# TC264MCUV02.net
KiCad netlist of a schematic drawn in Altium Designer
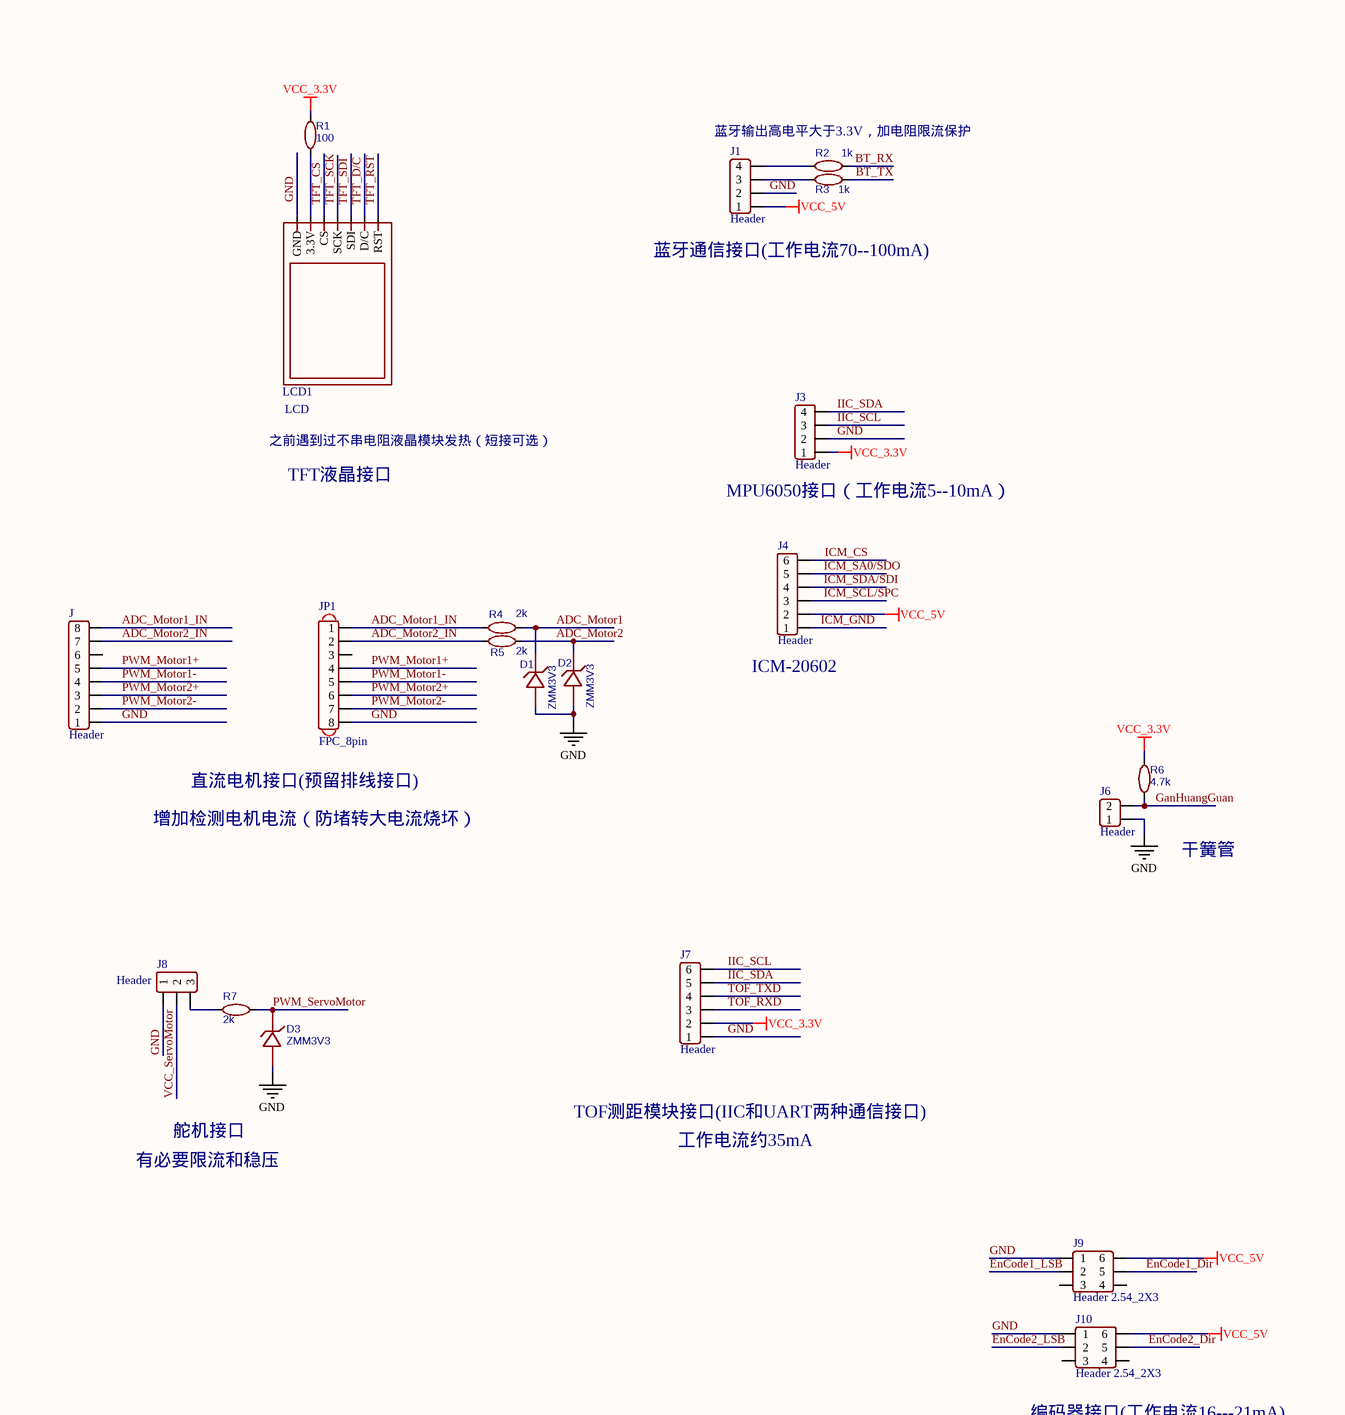
[diagram p0: TC264MCUV02.SchDoc, top left]
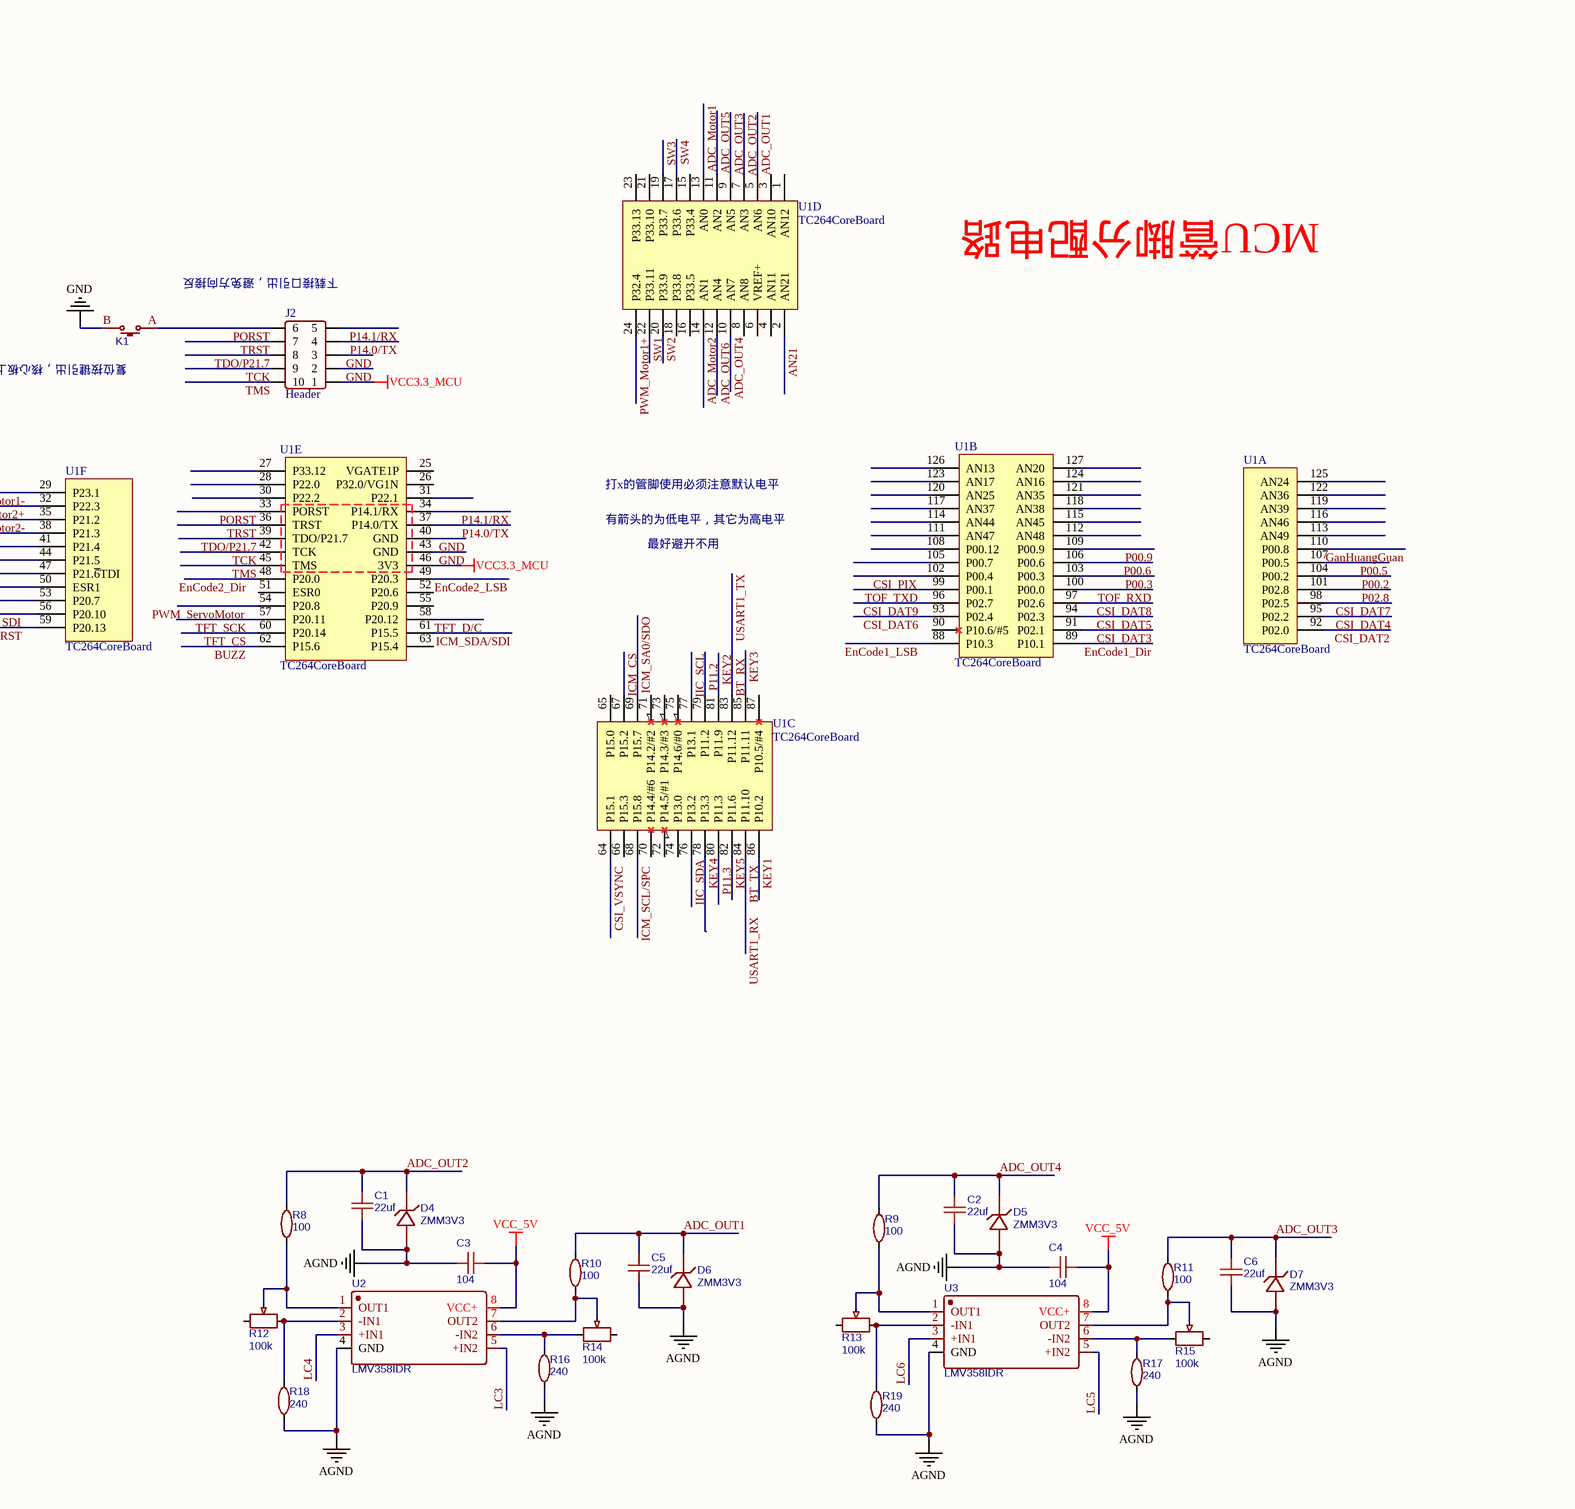
[diagram p1: TC264MCUV02.SchDoc, top right]
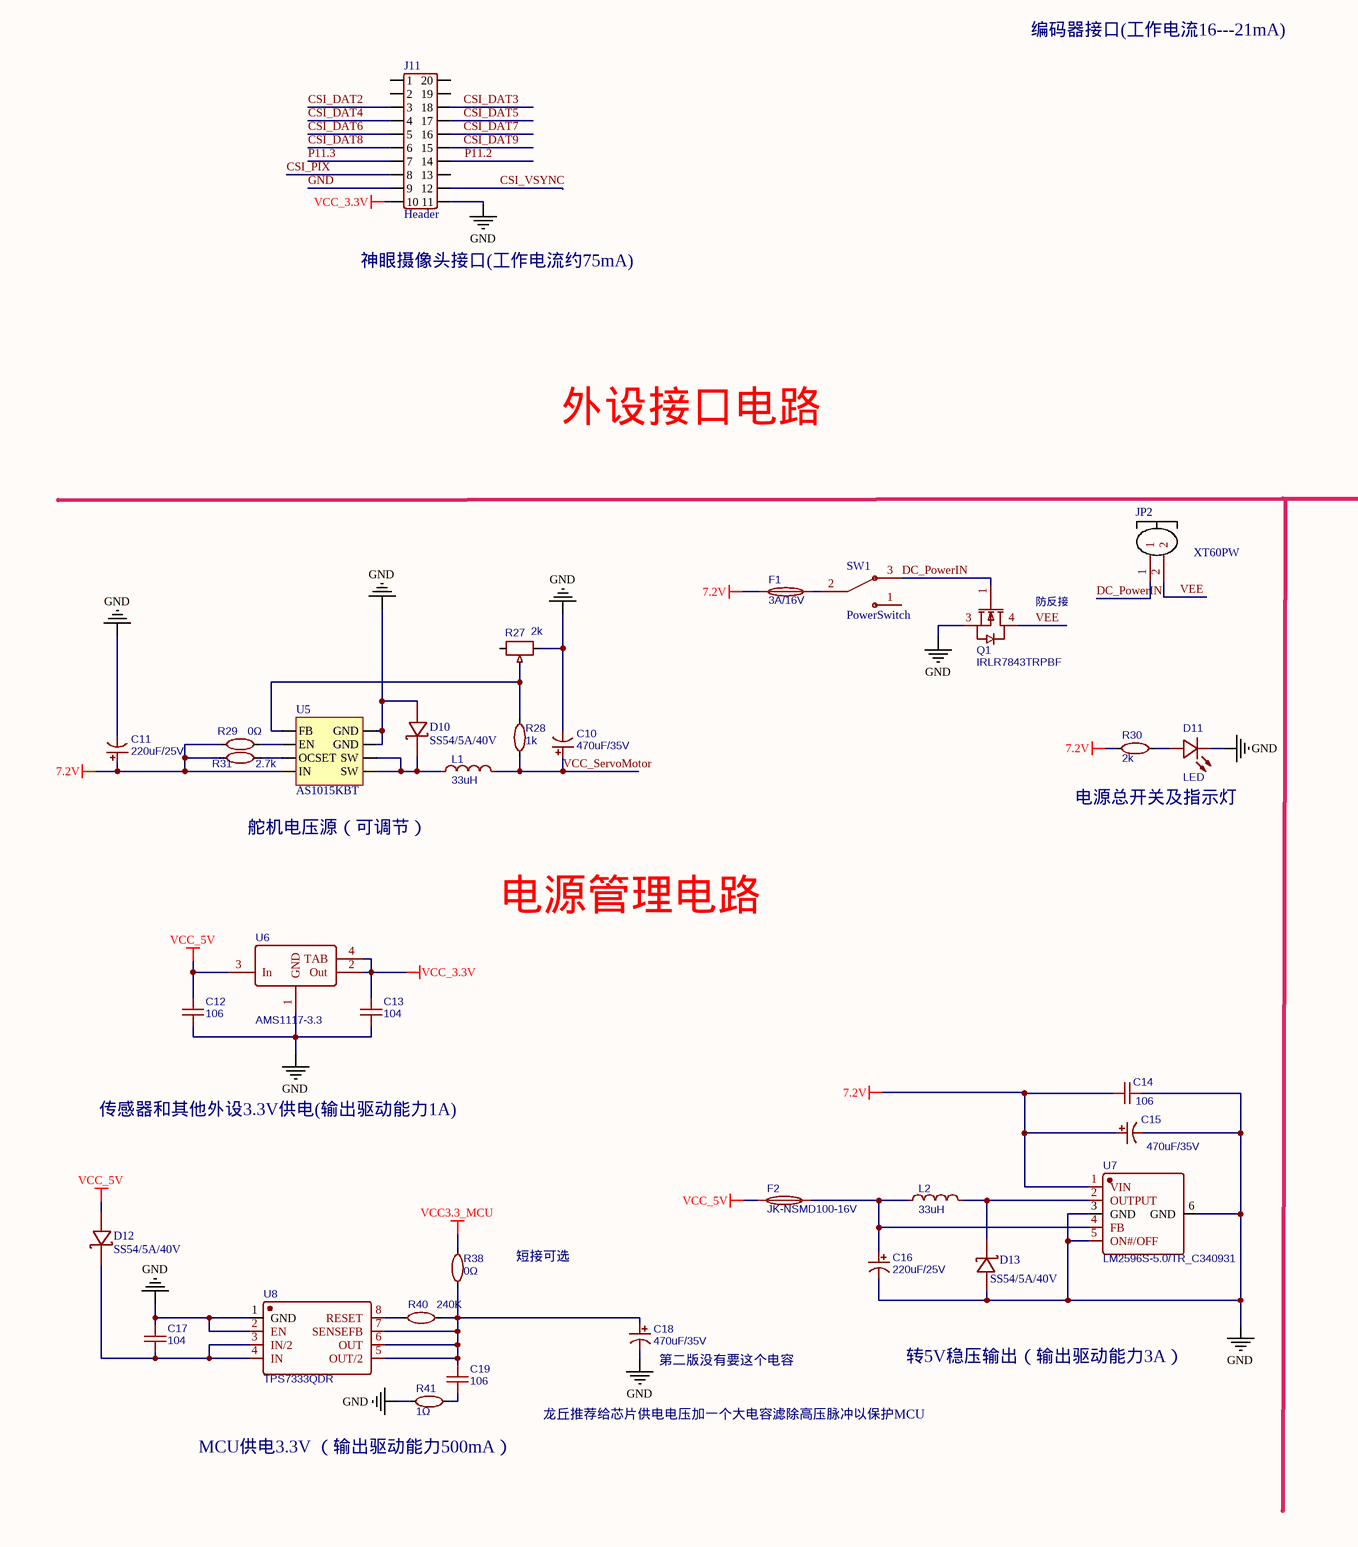
[diagram p2: TC264MCUV02.SchDoc, bottom left]
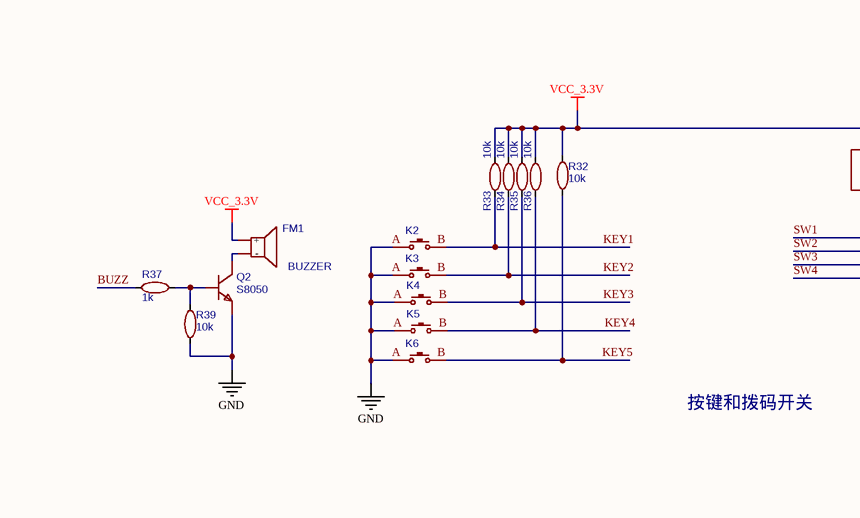
[diagram p3: TC264MCUV02.SchDoc, bottom middle]
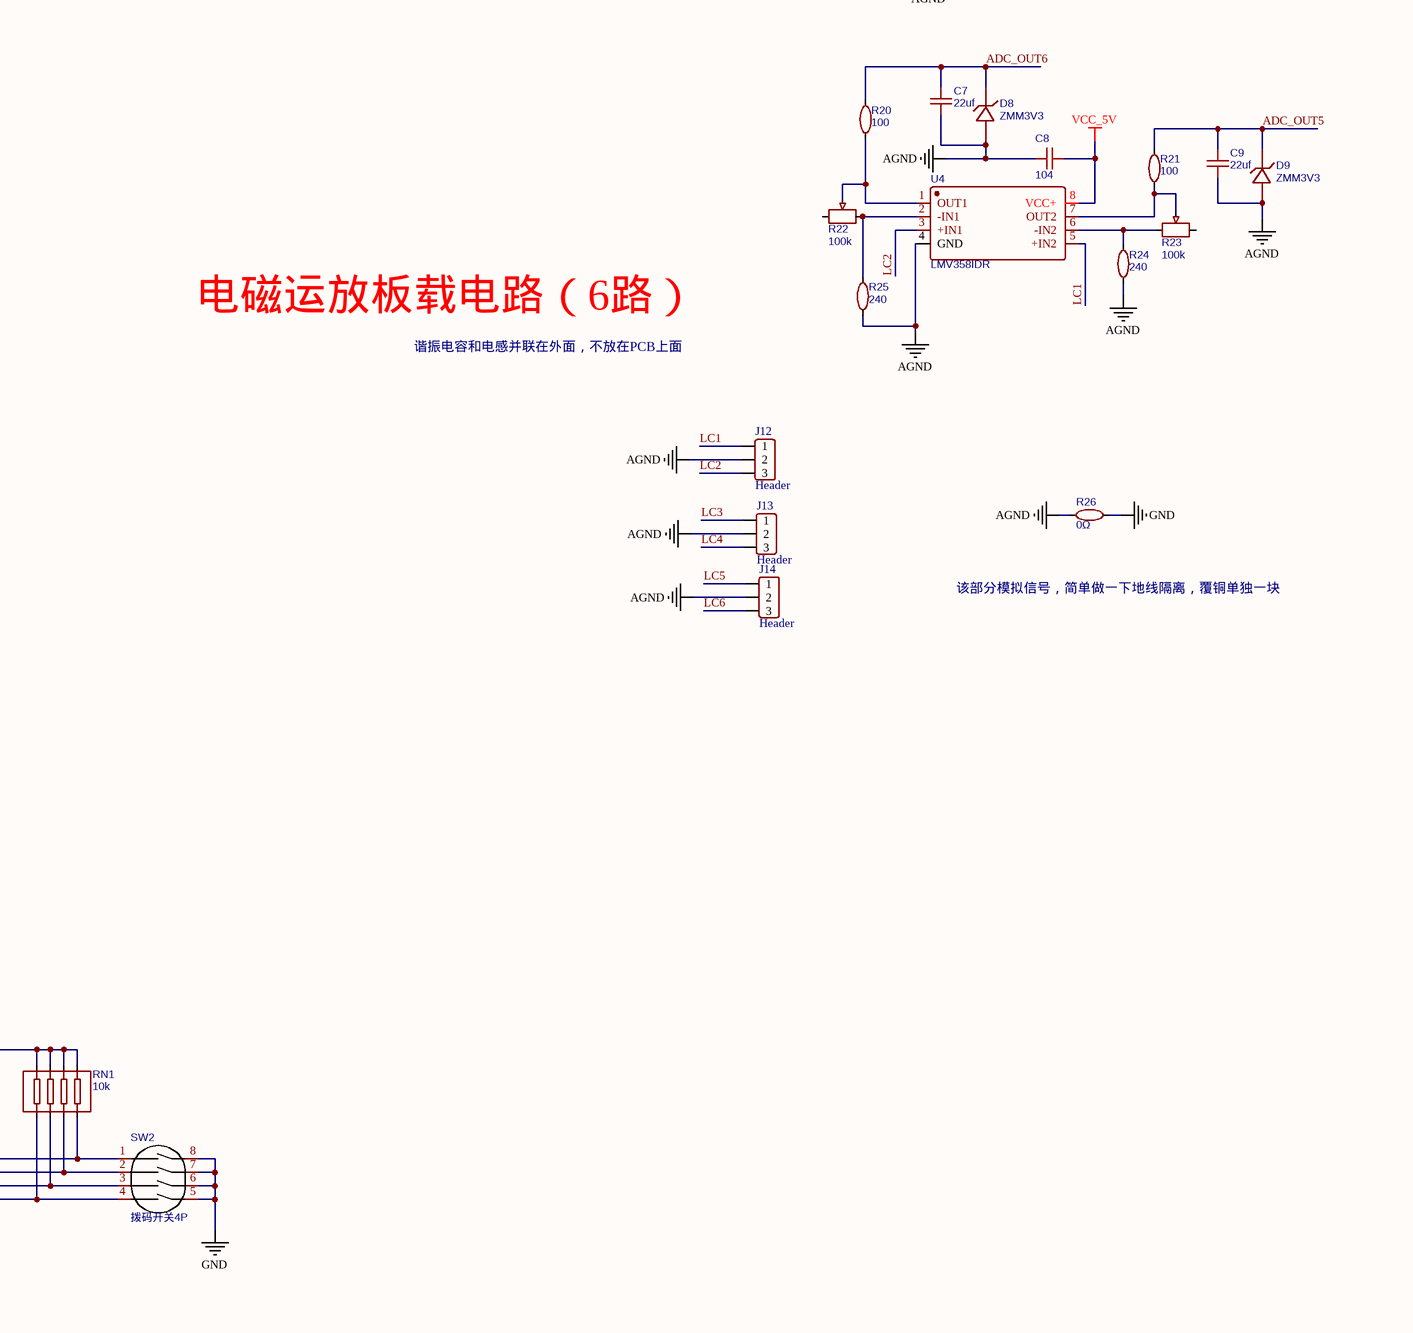
[diagram p4: TC264MCUV02.SchDoc, bottom right]

(export (version "E")
  (design (tool "Eeschema 10.0.6"))
  (components
    (comp (ref "C1")
      (value "22uf")
      (footprint "CAP_0603")
      (fields
        (field (name "BOM_SUPPLIER PART") "C307348")
        (field (name "BOM_MANUFACTURER PART") "CL10B104KB8WPNC")
        (field (name "CONTRIBUTOR") "LCSC")
      )
      (libsource (lib "LTC_Library1") (part "CAP_0603"))
    )
    (comp (ref "C2")
      (value "22uf")
      (footprint "CAP_0603")
      (fields
        (field (name "BOM_SUPPLIER PART") "C307348")
        (field (name "BOM_MANUFACTURER PART") "CL10B104KB8WPNC")
        (field (name "CONTRIBUTOR") "LCSC")
      )
      (libsource (lib "LTC_Library1") (part "CAP_0603"))
    )
    (comp (ref "C3")
      (value "104")
      (footprint "CAP_0603")
      (fields
        (field (name "BOM_SUPPLIER PART") "C307348")
        (field (name "BOM_MANUFACTURER PART") "CL10B104KB8WPNC")
        (field (name "CONTRIBUTOR") "LCSC")
      )
      (libsource (lib "LTC_Library1") (part "CAP_0603"))
    )
    (comp (ref "C4")
      (value "104")
      (footprint "CAP_0603")
      (fields
        (field (name "BOM_SUPPLIER PART") "C307348")
        (field (name "BOM_MANUFACTURER PART") "CL10B104KB8WPNC")
        (field (name "CONTRIBUTOR") "LCSC")
      )
      (libsource (lib "LTC_Library1") (part "CAP_0603"))
    )
    (comp (ref "C5")
      (value "22uf")
      (footprint "CAP_0603")
      (fields
        (field (name "BOM_SUPPLIER PART") "C307348")
        (field (name "BOM_MANUFACTURER PART") "CL10B104KB8WPNC")
        (field (name "CONTRIBUTOR") "LCSC")
      )
      (libsource (lib "LTC_Library1") (part "CAP_0603"))
    )
    (comp (ref "C6")
      (value "22uf")
      (footprint "CAP_0603")
      (fields
        (field (name "BOM_SUPPLIER PART") "C307348")
        (field (name "BOM_MANUFACTURER PART") "CL10B104KB8WPNC")
        (field (name "CONTRIBUTOR") "LCSC")
      )
      (libsource (lib "LTC_Library1") (part "CAP_0603"))
    )
    (comp (ref "C7")
      (value "22uf")
      (footprint "CAP_0603")
      (fields
        (field (name "BOM_SUPPLIER PART") "C307348")
        (field (name "BOM_MANUFACTURER PART") "CL10B104KB8WPNC")
        (field (name "CONTRIBUTOR") "LCSC")
      )
      (libsource (lib "LTC_Library1") (part "CAP_0603"))
    )
    (comp (ref "C8")
      (value "104")
      (footprint "CAP_0603")
      (fields
        (field (name "BOM_SUPPLIER PART") "C307348")
        (field (name "BOM_MANUFACTURER PART") "CL10B104KB8WPNC")
        (field (name "CONTRIBUTOR") "LCSC")
      )
      (libsource (lib "LTC_Library1") (part "CAP_0603"))
    )
    (comp (ref "C9")
      (value "22uf")
      (footprint "CAP_0603")
      (fields
        (field (name "BOM_SUPPLIER PART") "C307348")
        (field (name "BOM_MANUFACTURER PART") "CL10B104KB8WPNC")
        (field (name "CONTRIBUTOR") "LCSC")
      )
      (libsource (lib "LTC_Library1") (part "CAP_0603"))
    )
    (comp (ref "C10")
      (value "470uF/35V")
      (footprint "CAPE_SMD_F_8.4")
      (description "贴片电解电容")
      (fields
        (field (name "BOM_MANUFACTURER PART") "RVT1C221M0607")
        (field (name "BOM_SUPPLIER PART") "C72496")
      )
      (libsource (lib "") (part "CAP_E_SMD_1"))
    )
    (comp (ref "C11")
      (value "220uF/25V")
      (footprint "CAPE_SMD_F_8.4")
      (description "贴片电解电容")
      (fields
        (field (name "BOM_MANUFACTURER PART") "RVT1C221M0607")
        (field (name "BOM_SUPPLIER PART") "C72496")
      )
      (libsource (lib "") (part "CAP_E_SMD_1"))
    )
    (comp (ref "C12")
      (value "106")
      (footprint "CAP_0603")
      (fields
        (field (name "BOM_SUPPLIER PART") "C307348")
        (field (name "BOM_MANUFACTURER PART") "CL10B104KB8WPNC")
        (field (name "CONTRIBUTOR") "LCSC")
      )
      (libsource (lib "LTC_Library1") (part "CAP_0603"))
    )
    (comp (ref "C13")
      (value "104")
      (footprint "CAP_0603")
      (fields
        (field (name "BOM_SUPPLIER PART") "C307348")
        (field (name "BOM_MANUFACTURER PART") "CL10B104KB8WPNC")
        (field (name "CONTRIBUTOR") "LCSC")
      )
      (libsource (lib "LTC_Library1") (part "CAP_0603"))
    )
    (comp (ref "C14")
      (value "106")
      (footprint "CAP_0603")
      (fields
        (field (name "BOM_SUPPLIER PART") "C307348")
        (field (name "BOM_MANUFACTURER PART") "CL10B104KB8WPNC")
        (field (name "CONTRIBUTOR") "LCSC")
      )
      (libsource (lib "LTC_Library1") (part "CAP_0603"))
    )
    (comp (ref "C15")
      (value "470uF/35V")
      (footprint "CAPE_SMD_G_10.6")
      (description "贴片电解电容")
      (fields
        (field (name "BOM_MANUFACTURER PART") "RVT1C221M0607")
        (field (name "BOM_SUPPLIER PART") "C72496")
      )
      (libsource (lib "LTC_Library1") (part "CAP_E_SMD"))
    )
    (comp (ref "C16")
      (value "220uF/25V")
      (footprint "CAPE_SMD_F_8.4")
      (description "贴片电解电容")
      (fields
        (field (name "BOM_MANUFACTURER PART") "RVT1C221M0607")
        (field (name "BOM_SUPPLIER PART") "C72496")
      )
      (libsource (lib "") (part "CAP_E_SMD_1"))
    )
    (comp (ref "C17")
      (value "104")
      (footprint "CAP_0603")
      (fields
        (field (name "BOM_SUPPLIER PART") "C307348")
        (field (name "BOM_MANUFACTURER PART") "CL10B104KB8WPNC")
        (field (name "CONTRIBUTOR") "LCSC")
      )
      (libsource (lib "LTC_Library1") (part "CAP_0603"))
    )
    (comp (ref "C18")
      (value "470uF/35V")
      (footprint "CAPE_SMD_G_10.6")
      (description "贴片电解电容")
      (fields
        (field (name "BOM_MANUFACTURER PART") "RVT1C221M0607")
        (field (name "BOM_SUPPLIER PART") "C72496")
      )
      (libsource (lib "") (part "CAP_E_SMD_1"))
    )
    (comp (ref "C19")
      (value "106")
      (footprint "CAP_0603")
      (fields
        (field (name "BOM_SUPPLIER PART") "C307348")
        (field (name "BOM_MANUFACTURER PART") "CL10B104KB8WPNC")
        (field (name "CONTRIBUTOR") "LCSC")
      )
      (libsource (lib "LTC_Library1") (part "CAP_0603"))
    )
    (comp (ref "D1")
      (value "ZMM3V3")
      (footprint "LL-34_L3.5-W1.5-RD")
      (fields (field (name "BOM_SUPPLIER PART") "C8056"))
      (libsource (lib "SmartCar_Library") (part "ZMM3V3"))
    )
    (comp (ref "D2")
      (value "ZMM3V3")
      (footprint "LL-34_L3.5-W1.5-RD")
      (fields (field (name "BOM_SUPPLIER PART") "C8056"))
      (libsource (lib "SmartCar_Library") (part "ZMM3V3"))
    )
    (comp (ref "D3")
      (value "ZMM3V3")
      (footprint "LL-34_L3.5-W1.5-RD")
      (fields (field (name "BOM_SUPPLIER PART") "C8056"))
      (libsource (lib "SmartCar_Library") (part "ZMM3V3"))
    )
    (comp (ref "D4")
      (value "ZMM3V3")
      (footprint "LL-34_L3.5-W1.5-RD")
      (fields (field (name "BOM_SUPPLIER PART") "C8056"))
      (libsource (lib "SmartCar_Library") (part "ZMM3V3"))
    )
    (comp (ref "D5")
      (value "ZMM3V3")
      (footprint "LL-34_L3.5-W1.5-RD")
      (fields (field (name "BOM_SUPPLIER PART") "C8056"))
      (libsource (lib "SmartCar_Library") (part "ZMM3V3"))
    )
    (comp (ref "D6")
      (value "ZMM3V3")
      (footprint "LL-34_L3.5-W1.5-RD")
      (fields (field (name "BOM_SUPPLIER PART") "C8056"))
      (libsource (lib "SmartCar_Library") (part "ZMM3V3"))
    )
    (comp (ref "D7")
      (value "ZMM3V3")
      (footprint "LL-34_L3.5-W1.5-RD")
      (fields (field (name "BOM_SUPPLIER PART") "C8056"))
      (libsource (lib "SmartCar_Library") (part "ZMM3V3"))
    )
    (comp (ref "D8")
      (value "ZMM3V3")
      (footprint "LL-34_L3.5-W1.5-RD")
      (fields (field (name "BOM_SUPPLIER PART") "C8056"))
      (libsource (lib "SmartCar_Library") (part "ZMM3V3"))
    )
    (comp (ref "D9")
      (value "ZMM3V3")
      (footprint "LL-34_L3.5-W1.5-RD")
      (fields (field (name "BOM_SUPPLIER PART") "C8056"))
      (libsource (lib "SmartCar_Library") (part "ZMM3V3"))
    )
    (comp (ref "D10")
      (value "SS54/5A/40V")
      (footprint "DO214_SMA")
      (libsource (lib "LTC_Library1") (part "SS54"))
    )
    (comp (ref "D11")
      (value "LED")
      (footprint "LED_0603_B")
      (description "发光LED")
      (fields
        (field (name "BOM_MANUFACTURER PART") "D-G080508G1")
        (field (name "BOM_SUPPLIER PART") "C107402")
        (field (name "CONTRIBUTOR") "LCSC")
      )
      (libsource (lib "LTC_Library1") (part "LED_0603"))
    )
    (comp (ref "D12")
      (value "SS54/5A/40V")
      (footprint "DO214_SMA")
      (libsource (lib "LTC_Library1") (part "SS54"))
    )
    (comp (ref "D13")
      (value "SS54/5A/40V")
      (footprint "DO214_SMA")
      (libsource (lib "LTC_Library1") (part "SS54"))
    )
    (comp (ref "F1")
      (value "3A/16V")
      (footprint "FUSE_1210")
      (fields
        (field (name "BOM_SUPPLIER PART") "C369161")
        (field (name "BOM_MANUFACTURER PART") "JK-NSMD100-16V")
        (field (name "CONTRIBUTOR") "LCSC")
      )
      (libsource (lib "SmartCar_Library") (part "JK-NSMD100-16V"))
    )
    (comp (ref "F2")
      (value "JK-NSMD100-16V")
      (footprint "F1206")
      (fields (field (name "BOM_SUPPLIER PART") "C369161") (field (name "CONTRIBUTOR") "LCSC"))
      (libsource (lib "SmartCar_Library") (part "JK-NSMD100-16V"))
    )
    (comp (ref "FM1")
      (value "BUZZER")
      (footprint "BUZZ-12*7.5")
      (description "蜂鸣器")
      (fields (field (name "BOM_MANUFACTURER PART") "TMB12A12") (field (name "BOM_SUPPLIER PART") "C96079"))
      (libsource (lib "LTC_Library1") (part "BUZZER"))
    )
    (comp (ref "J")
      (value "Header")
      (footprint "Header 2.54X8")
      (libsource (lib "LTC_Library1") (part "Header 2.54_8"))
    )
    (comp (ref "J1")
      (value "Header")
      (footprint "Header F 2.54X4")
      (libsource (lib "LTC_Library1") (part "Header 2.54_4"))
    )
    (comp (ref "J2")
      (value "Header")
      (footprint "IDC_10P")
      (libsource (lib "Headers") (part "Header 2.54_2X5"))
    )
    (comp (ref "J3")
      (value "Header")
      (footprint "Header 2.54X4")
      (libsource (lib "LTC_Library1") (part "Header 2.54_4"))
    )
    (comp (ref "J4")
      (value "Header")
      (footprint "Header 2.54X6")
      (libsource (lib "LTC_Library1") (part "Header 2.54_6"))
    )
    (comp (ref "J6")
      (value "Header")
      (footprint "HX2.54-2")
      (libsource (lib "LTC_Library1") (part "Header 2.54_2"))
    )
    (comp (ref "J7")
      (value "Header")
      (footprint "Header 2.54X6")
      (libsource (lib "LTC_Library1") (part "Header 2.54_6"))
    )
    (comp (ref "J8")
      (value "Header")
      (footprint "Header 2.54X3")
      (libsource (lib "LTC_Library1") (part "Header 2.54_3"))
    )
    (comp (ref "J9")
      (value "Header 2.54_2X3")
      (footprint "IDC_6P")
      (libsource (lib "Headers") (part "Header 2.54_2X3"))
    )
    (comp (ref "J10")
      (value "Header 2.54_2X3")
      (footprint "IDC_6P")
      (libsource (lib "Headers") (part "Header 2.54_2X3"))
    )
    (comp (ref "J11")
      (value "Header")
      (footprint "Header F 2.54_2x10")
      (libsource (lib "LTC_Library1") (part "Header 2.54_2X10"))
    )
    (comp (ref "J12")
      (value "Header")
      (footprint "Header 2.54X3")
      (libsource (lib "LTC_Library1") (part "Header 2.54_3"))
    )
    (comp (ref "J13")
      (value "Header")
      (footprint "Header 2.54X3")
      (libsource (lib "LTC_Library1") (part "Header 2.54_3"))
    )
    (comp (ref "J14")
      (value "Header")
      (footprint "Header 2.54X3")
      (libsource (lib "LTC_Library1") (part "Header 2.54_3"))
    )
    (comp (ref "JP1")
      (value "FPC_8pin")
      (footprint "FPC_1.0_8P")
      (libsource (lib "LTC_Library1") (part "FPC_8pin"))
    )
    (comp (ref "JP2")
      (value "XT60PW")
      (footprint "XT60PW")
      (libsource (lib "SmartCar_Library") (part "XT60PW"))
    )
    (comp (ref "K1")
      (value "TS-Button_2P")
      (footprint "SW_SMD_6.1*3.7")
      (description "贴片按键 3*6*2.5")
      (fields
        (field (name "BOM_SUPPLIER PART") "C455236")
        (field (name "BOM_MANUFACTURER PART") "TS-1007S-26")
        (field (name "CONTRIBUTOR") "LCSC")
      )
      (libsource (lib "LTC_Library1") (part "TS-Button_2P"))
    )
    (comp (ref "K2")
      (value "TS-Button_2P")
      (footprint "SW_SMD_6.1*3.7")
      (description "贴片按键 3*6*2.5")
      (fields
        (field (name "BOM_SUPPLIER PART") "C455236")
        (field (name "BOM_MANUFACTURER PART") "TS-1007S-26")
        (field (name "CONTRIBUTOR") "LCSC")
      )
      (libsource (lib "LTC_Library1") (part "TS-Button_2P"))
    )
    (comp (ref "K3")
      (value "TS-Button_2P")
      (footprint "SW_SMD_6.1*3.7")
      (description "贴片按键 3*6*2.5")
      (fields
        (field (name "BOM_SUPPLIER PART") "C455236")
        (field (name "BOM_MANUFACTURER PART") "TS-1007S-26")
        (field (name "CONTRIBUTOR") "LCSC")
      )
      (libsource (lib "LTC_Library1") (part "TS-Button_2P"))
    )
    (comp (ref "K4")
      (value "TS-Button_2P")
      (footprint "SW_SMD_6.1*3.7")
      (description "贴片按键 3*6*2.5")
      (fields
        (field (name "BOM_SUPPLIER PART") "C455236")
        (field (name "BOM_MANUFACTURER PART") "TS-1007S-26")
        (field (name "CONTRIBUTOR") "LCSC")
      )
      (libsource (lib "LTC_Library1") (part "TS-Button_2P"))
    )
    (comp (ref "K5")
      (value "TS-Button_2P")
      (footprint "SW_SMD_6.1*3.7")
      (description "贴片按键 3*6*2.5")
      (fields
        (field (name "BOM_SUPPLIER PART") "C455236")
        (field (name "BOM_MANUFACTURER PART") "TS-1007S-26")
        (field (name "CONTRIBUTOR") "LCSC")
      )
      (libsource (lib "LTC_Library1") (part "TS-Button_2P"))
    )
    (comp (ref "K6")
      (value "TS-Button_2P")
      (footprint "SW_SMD_6.1*3.7")
      (description "贴片按键 3*6*2.5")
      (fields
        (field (name "BOM_SUPPLIER PART") "C455236")
        (field (name "BOM_MANUFACTURER PART") "TS-1007S-26")
        (field (name "CONTRIBUTOR") "LCSC")
      )
      (libsource (lib "LTC_Library1") (part "TS-Button_2P"))
    )
    (comp (ref "L1")
      (value "33uH")
      (footprint "IND-SMD_L8.0-W8.0")
      (fields
        (field (name "BOM_SUPPLIER PART") "C295130")
        (field (name "BOM_MANUFACTURER PART") "NLV25T-330J-EF")
        (field (name "CONTRIBUTOR") "LCSC")
      )
      (libsource (lib "SmartCar_Library") (part "Inductor"))
    )
    (comp (ref "L2")
      (value "33uH")
      (footprint "IND-SMD_L8.0-W8.0")
      (fields
        (field (name "BOM_SUPPLIER PART") "C295130")
        (field (name "BOM_MANUFACTURER PART") "NLV25T-330J-EF")
        (field (name "CONTRIBUTOR") "LCSC")
      )
      (libsource (lib "SmartCar_Library") (part "Inductor"))
    )
    (comp (ref "LCD1")
      (value "LCD")
      (footprint "TFT_LCD")
      (libsource (lib "SmartCar_Library") (part "TFT-LCD"))
    )
    (comp (ref "Q1")
      (value "IRLR7843TRPBF")
      (footprint "TO-252-2")
      (description "MOS管")
      (fields (field (name "BOM_SUPPLIER PART") "C21988"))
      (libsource (lib "LTC_Library1") (part "IRLR7843TRPBF"))
    )
    (comp (ref "Q2")
      (value "S8050")
      (footprint "SOT-23-3")
      (description "三极管NPN")
      (fields
        (field (name "BOM_MANUFACTURER PART") "FHT9014Y-ME")
        (field (name "BOM_SUPPLIER PART") "C88861")
      )
      (libsource (lib "LTC_Library1") (part "S8050"))
    )
    (comp (ref "R1")
      (value "100")
      (footprint "RES_0603")
      (fields
        (field (name "BOM_MANUFACTURER PART") "RC0402JR-07100KL")
        (field (name "BOM_SUPPLIER PART") "C106234")
      )
      (libsource (lib "LTC_Library1") (part "RES_0603"))
    )
    (comp (ref "R2")
      (value "1k")
      (footprint "RES_0603")
      (fields
        (field (name "BOM_MANUFACTURER PART") "RC0402JR-07100KL")
        (field (name "BOM_SUPPLIER PART") "C106234")
      )
      (libsource (lib "LTC_Library1") (part "RES_0603"))
    )
    (comp (ref "R3")
      (value "1k")
      (footprint "RES_0603")
      (fields
        (field (name "BOM_MANUFACTURER PART") "RC0402JR-07100KL")
        (field (name "BOM_SUPPLIER PART") "C106234")
      )
      (libsource (lib "LTC_Library1") (part "RES_0603"))
    )
    (comp (ref "R4")
      (value "2k")
      (footprint "RES_0603")
      (fields
        (field (name "BOM_MANUFACTURER PART") "RC0402JR-07100KL")
        (field (name "BOM_SUPPLIER PART") "C106234")
      )
      (libsource (lib "LTC_Library1") (part "RES_0603"))
    )
    (comp (ref "R5")
      (value "2k")
      (footprint "RES_0603")
      (fields
        (field (name "BOM_MANUFACTURER PART") "RC0402JR-07100KL")
        (field (name "BOM_SUPPLIER PART") "C106234")
      )
      (libsource (lib "LTC_Library1") (part "RES_0603"))
    )
    (comp (ref "R6")
      (value "4.7k")
      (footprint "RES_0603")
      (fields
        (field (name "BOM_MANUFACTURER PART") "RC0402JR-07100KL")
        (field (name "BOM_SUPPLIER PART") "C106234")
      )
      (libsource (lib "LTC_Library1") (part "RES_0603"))
    )
    (comp (ref "R7")
      (value "2k")
      (footprint "RES_0603")
      (fields
        (field (name "BOM_MANUFACTURER PART") "RC0402JR-07100KL")
        (field (name "BOM_SUPPLIER PART") "C106234")
      )
      (libsource (lib "LTC_Library1") (part "RES_0603"))
    )
    (comp (ref "R8")
      (value "100")
      (footprint "RES_0603")
      (fields
        (field (name "BOM_MANUFACTURER PART") "RC0402JR-07100KL")
        (field (name "BOM_SUPPLIER PART") "C106234")
      )
      (libsource (lib "LTC_Library1") (part "RES_0603"))
    )
    (comp (ref "R9")
      (value "100")
      (footprint "RES_0603")
      (fields
        (field (name "BOM_MANUFACTURER PART") "RC0402JR-07100KL")
        (field (name "BOM_SUPPLIER PART") "C106234")
      )
      (libsource (lib "LTC_Library1") (part "RES_0603"))
    )
    (comp (ref "R10")
      (value "100")
      (footprint "RES_0603")
      (fields
        (field (name "BOM_MANUFACTURER PART") "RC0402JR-07100KL")
        (field (name "BOM_SUPPLIER PART") "C106234")
      )
      (libsource (lib "LTC_Library1") (part "RES_0603"))
    )
    (comp (ref "R11")
      (value "100")
      (footprint "RES_0603")
      (fields
        (field (name "BOM_MANUFACTURER PART") "RC0402JR-07100KL")
        (field (name "BOM_SUPPLIER PART") "C106234")
      )
      (libsource (lib "LTC_Library1") (part "RES_0603"))
    )
    (comp (ref "R12")
      (value "100k")
      (footprint "RES_POT-3296W")
      (description "可调电阻3296W")
      (fields
        (field (name "BOM_SUPPLIER PART") "C118963")
        (field (name "BOM_MANUFACTURER PART") "3296W-1-104")
        (field (name "CONTRIBUTOR") "LCSC")
      )
      (libsource (lib "LTC_Library1") (part "RES_POT-3296W"))
    )
    (comp (ref "R13")
      (value "100k")
      (footprint "RES_POT-3296W")
      (description "可调电阻3296W")
      (fields
        (field (name "BOM_SUPPLIER PART") "C118963")
        (field (name "BOM_MANUFACTURER PART") "3296W-1-104")
        (field (name "CONTRIBUTOR") "LCSC")
      )
      (libsource (lib "LTC_Library1") (part "RES_POT-3296W"))
    )
    (comp (ref "R14")
      (value "100k")
      (footprint "RES_POT-3296W")
      (description "可调电阻3296W")
      (fields
        (field (name "BOM_SUPPLIER PART") "C118963")
        (field (name "BOM_MANUFACTURER PART") "3296W-1-104")
        (field (name "CONTRIBUTOR") "LCSC")
      )
      (libsource (lib "LTC_Library1") (part "RES_POT-3296W"))
    )
    (comp (ref "R15")
      (value "100k")
      (footprint "RES_POT-3296W")
      (description "可调电阻3296W")
      (fields
        (field (name "BOM_SUPPLIER PART") "C118963")
        (field (name "BOM_MANUFACTURER PART") "3296W-1-104")
        (field (name "CONTRIBUTOR") "LCSC")
      )
      (libsource (lib "LTC_Library1") (part "RES_POT-3296W"))
    )
    (comp (ref "R16")
      (value "240")
      (footprint "RES_0603")
      (fields
        (field (name "BOM_MANUFACTURER PART") "RC0402JR-07100KL")
        (field (name "BOM_SUPPLIER PART") "C106234")
      )
      (libsource (lib "LTC_Library1") (part "RES_0603"))
    )
    (comp (ref "R17")
      (value "240")
      (footprint "RES_0603")
      (fields
        (field (name "BOM_MANUFACTURER PART") "RC0402JR-07100KL")
        (field (name "BOM_SUPPLIER PART") "C106234")
      )
      (libsource (lib "LTC_Library1") (part "RES_0603"))
    )
    (comp (ref "R18")
      (value "240")
      (footprint "RES_0603")
      (fields
        (field (name "BOM_MANUFACTURER PART") "RC0402JR-07100KL")
        (field (name "BOM_SUPPLIER PART") "C106234")
      )
      (libsource (lib "LTC_Library1") (part "RES_0603"))
    )
    (comp (ref "R19")
      (value "240")
      (footprint "RES_0603")
      (fields
        (field (name "BOM_MANUFACTURER PART") "RC0402JR-07100KL")
        (field (name "BOM_SUPPLIER PART") "C106234")
      )
      (libsource (lib "LTC_Library1") (part "RES_0603"))
    )
    (comp (ref "R20")
      (value "100")
      (footprint "RES_0603")
      (fields
        (field (name "BOM_MANUFACTURER PART") "RC0402JR-07100KL")
        (field (name "BOM_SUPPLIER PART") "C106234")
      )
      (libsource (lib "LTC_Library1") (part "RES_0603"))
    )
    (comp (ref "R21")
      (value "100")
      (footprint "RES_0603")
      (fields
        (field (name "BOM_MANUFACTURER PART") "RC0402JR-07100KL")
        (field (name "BOM_SUPPLIER PART") "C106234")
      )
      (libsource (lib "LTC_Library1") (part "RES_0603"))
    )
    (comp (ref "R22")
      (value "100k")
      (footprint "RES_POT-3296W")
      (description "可调电阻3296W")
      (fields
        (field (name "BOM_SUPPLIER PART") "C118963")
        (field (name "BOM_MANUFACTURER PART") "3296W-1-104")
        (field (name "CONTRIBUTOR") "LCSC")
      )
      (libsource (lib "LTC_Library1") (part "RES_POT-3296W"))
    )
    (comp (ref "R23")
      (value "100k")
      (footprint "RES_POT-3296W")
      (description "可调电阻3296W")
      (fields
        (field (name "BOM_SUPPLIER PART") "C118963")
        (field (name "BOM_MANUFACTURER PART") "3296W-1-104")
        (field (name "CONTRIBUTOR") "LCSC")
      )
      (libsource (lib "LTC_Library1") (part "RES_POT-3296W"))
    )
    (comp (ref "R24")
      (value "240")
      (footprint "RES_0603")
      (fields
        (field (name "BOM_MANUFACTURER PART") "RC0402JR-07100KL")
        (field (name "BOM_SUPPLIER PART") "C106234")
      )
      (libsource (lib "LTC_Library1") (part "RES_0603"))
    )
    (comp (ref "R25")
      (value "240")
      (footprint "RES_0603")
      (fields
        (field (name "BOM_MANUFACTURER PART") "RC0402JR-07100KL")
        (field (name "BOM_SUPPLIER PART") "C106234")
      )
      (libsource (lib "LTC_Library1") (part "RES_0603"))
    )
    (comp (ref "R26")
      (value "0Ω")
      (footprint "RES_0603")
      (fields
        (field (name "BOM_MANUFACTURER PART") "RC0402JR-07100KL")
        (field (name "BOM_SUPPLIER PART") "C106234")
      )
      (libsource (lib "LTC_Library1") (part "RES_0603"))
    )
    (comp (ref "R27")
      (value "2k")
      (footprint "RES_POT-3296W")
      (description "可调电阻3296W")
      (fields
        (field (name "BOM_SUPPLIER PART") "C118963")
        (field (name "BOM_MANUFACTURER PART") "3296W-1-104")
        (field (name "CONTRIBUTOR") "LCSC")
      )
      (libsource (lib "LTC_Library1") (part "RES_POT-3296W"))
    )
    (comp (ref "R28")
      (value "1k")
      (footprint "RES_0603")
      (fields
        (field (name "BOM_MANUFACTURER PART") "RC0402JR-07100KL")
        (field (name "BOM_SUPPLIER PART") "C106234")
      )
      (libsource (lib "LTC_Library1") (part "RES_0603"))
    )
    (comp (ref "R29")
      (value "0Ω")
      (footprint "RES_0603")
      (fields
        (field (name "BOM_MANUFACTURER PART") "RC0402JR-07100KL")
        (field (name "BOM_SUPPLIER PART") "C106234")
      )
      (libsource (lib "LTC_Library1") (part "RES_0603"))
    )
    (comp (ref "R30")
      (value "2k")
      (footprint "RES_0603")
      (fields
        (field (name "BOM_MANUFACTURER PART") "RC0402JR-07100KL")
        (field (name "BOM_SUPPLIER PART") "C106234")
      )
      (libsource (lib "LTC_Library1") (part "RES_0603"))
    )
    (comp (ref "R31")
      (value "2.7k")
      (footprint "RES_0603")
      (fields
        (field (name "BOM_MANUFACTURER PART") "RC0402JR-07100KL")
        (field (name "BOM_SUPPLIER PART") "C106234")
      )
      (libsource (lib "LTC_Library1") (part "RES_0603"))
    )
    (comp (ref "R32")
      (value "10k")
      (footprint "RES_0603")
      (fields
        (field (name "BOM_MANUFACTURER PART") "RC0402JR-07100KL")
        (field (name "BOM_SUPPLIER PART") "C106234")
      )
      (libsource (lib "LTC_Library1") (part "RES_0603"))
    )
    (comp (ref "R33")
      (value "10k")
      (footprint "RES_0603")
      (fields
        (field (name "BOM_MANUFACTURER PART") "RC0402JR-07100KL")
        (field (name "BOM_SUPPLIER PART") "C106234")
      )
      (libsource (lib "LTC_Library1") (part "RES_0603"))
    )
    (comp (ref "R34")
      (value "10k")
      (footprint "RES_0603")
      (fields
        (field (name "BOM_MANUFACTURER PART") "RC0402JR-07100KL")
        (field (name "BOM_SUPPLIER PART") "C106234")
      )
      (libsource (lib "LTC_Library1") (part "RES_0603"))
    )
    (comp (ref "R35")
      (value "10k")
      (footprint "RES_0603")
      (fields
        (field (name "BOM_MANUFACTURER PART") "RC0402JR-07100KL")
        (field (name "BOM_SUPPLIER PART") "C106234")
      )
      (libsource (lib "LTC_Library1") (part "RES_0603"))
    )
    (comp (ref "R36")
      (value "10k")
      (footprint "RES_0603")
      (fields
        (field (name "BOM_MANUFACTURER PART") "RC0402JR-07100KL")
        (field (name "BOM_SUPPLIER PART") "C106234")
      )
      (libsource (lib "LTC_Library1") (part "RES_0603"))
    )
    (comp (ref "R37")
      (value "1k")
      (footprint "RES_0603")
      (fields
        (field (name "BOM_MANUFACTURER PART") "RC0402JR-07100KL")
        (field (name "BOM_SUPPLIER PART") "C106234")
      )
      (libsource (lib "LTC_Library1") (part "RES_0603"))
    )
    (comp (ref "R38")
      (value "0Ω")
      (footprint "RES_0603")
      (fields
        (field (name "BOM_MANUFACTURER PART") "RC0402JR-07100KL")
        (field (name "BOM_SUPPLIER PART") "C106234")
      )
      (libsource (lib "LTC_Library1") (part "RES_0603"))
    )
    (comp (ref "R39")
      (value "10k")
      (footprint "RES_0603")
      (fields
        (field (name "BOM_MANUFACTURER PART") "RC0402JR-07100KL")
        (field (name "BOM_SUPPLIER PART") "C106234")
      )
      (libsource (lib "LTC_Library1") (part "RES_0603"))
    )
    (comp (ref "R40")
      (value "240K")
      (footprint "RES_0603")
      (fields
        (field (name "BOM_MANUFACTURER PART") "RC0402JR-07100KL")
        (field (name "BOM_SUPPLIER PART") "C106234")
      )
      (libsource (lib "LTC_Library1") (part "RES_0603"))
    )
    (comp (ref "R41")
      (value "1Ω")
      (footprint "RES_0603")
      (fields
        (field (name "BOM_MANUFACTURER PART") "RC0402JR-07100KL")
        (field (name "BOM_SUPPLIER PART") "C106234")
      )
      (libsource (lib "LTC_Library1") (part "RES_0603"))
    )
    (comp (ref "RN1")
      (value "10k")
      (footprint "RES-ARRAY-SMD_0603-8P-L3.2-W1.6-BL")
      (fields
        (field (name "BOM_MANUFACTURER PART") "YC164-JR-0710KL")
        (field (name "BOM_SUPPLIER PART") "C107374")
      )
      (libsource (lib "SmartCar_Library") (part "RESW4"))
    )
    (comp (ref "SW1")
      (value "PowerSwitch")
      (footprint "SW-TH_K3-1260D-K1")
      (libsource (lib "SmartCar_Library") (part "PowerSwitch"))
    )
    (comp (ref "SW2")
      (value "拨码开关4P")
      (footprint "VDG/S-04HG-R")
      (description "DIP_4PX2*2.54")
      (fields
        (field (name "BOM_MANUFACTURER PART") "VDG/S-04HG-R")
        (field (name "BOM_SUPPLIER PART") "C15781")
      )
      (libsource (lib "LTC_Library1") (part "拨码开关4P"))
    )
    (comp (ref "U1")
      (value "TC264CoreBoard")
      (footprint "LQ-TC264-SYSVC-S")
      (libsource (lib "SmartCar_Library") (part "TC264CoreBoard"))
    )
    (comp (ref "U2")
      (value "LMV358IDR")
      (footprint "SOIC-8_150MIL")
      (fields (field (name "BOM_SUPPLIER PART") "C63813"))
      (libsource (lib "LTC_Library1") (part "LMV358IDR"))
    )
    (comp (ref "U3")
      (value "LMV358IDR")
      (footprint "SOIC-8_150MIL")
      (fields (field (name "BOM_SUPPLIER PART") "C63813"))
      (libsource (lib "LTC_Library1") (part "LMV358IDR"))
    )
    (comp (ref "U4")
      (value "LMV358IDR")
      (footprint "SOIC-8_150MIL")
      (fields (field (name "BOM_SUPPLIER PART") "C63813"))
      (libsource (lib "LTC_Library1") (part "LMV358IDR"))
    )
    (comp (ref "U5")
      (value "AS1015KBT")
      (footprint "SOIC-8_150MIL")
      (libsource (lib "SmartCar_Library") (part "AS1015KBT"))
    )
    (comp (ref "U6")
      (value "AMS1117-3.3")
      (footprint "SOT-223_3")
      (fields (field (name "BOM_SUPPLIER PART") "C165482") (field (name "CONTRIBUTOR") "LCSC"))
      (libsource (lib "LTC_Library1") (part "AMS1117-3.3"))
    )
    (comp (ref "U7")
      (value "LM2596S-5.0/TR_C340931")
      (footprint "TO-263_5")
      (fields
        (field (name "BOM_SUPPLIER PART") "C340931")
        (field (name "BOM_MANUFACTURER PART") "LM2596S-5.0/TR")
        (field (name "CONTRIBUTOR") "LCSC")
      )
      (libsource (lib "LTC_Library1") (part "LM2596S-5.0/TR_C340931"))
    )
    (comp (ref "U8")
      (value "TPS7333QDR")
      (footprint "SOIC-8_150MIL")
      (fields (field (name "BOM_SUPPLIER PART") "C23791"))
      (libsource (lib "LTC_Library1") (part "TPS7333QDR"))
    )
  )
  (nets
    (net (code "1") (name "/ADC_Motor1") (class "Default")
      (node (ref "D1") (pin "1") (pinfunction "C_1") (pintype "passive"))
      (node (ref "R4") (pin "1") (pinfunction "1_1") (pintype "passive"))
      (node (ref "U1") (pin "13") (pinfunction "AN0_13") (pintype "passive"))
    )
    (net (code "2") (name "/ADC_Motor1_IN") (class "Default")
      (node (ref "J") (pin "8") (pinfunction "8_8") (pintype "passive"))
      (node (ref "JP1") (pin "1") (pinfunction "1_1") (pintype "passive"))
      (node (ref "R4") (pin "2") (pinfunction "2_2") (pintype "passive"))
    )
    (net (code "3") (name "/ADC_Motor2") (class "Default")
      (node (ref "D2") (pin "1") (pinfunction "C_1") (pintype "passive"))
      (node (ref "R5") (pin "1") (pinfunction "1_1") (pintype "passive"))
      (node (ref "U1") (pin "14") (pinfunction "AN1_14") (pintype "passive"))
    )
    (net (code "4") (name "/ADC_Motor2_IN") (class "Default")
      (node (ref "J") (pin "7") (pinfunction "7_7") (pintype "passive"))
      (node (ref "JP1") (pin "2") (pinfunction "2_2") (pintype "passive"))
      (node (ref "R5") (pin "2") (pinfunction "2_2") (pintype "passive"))
    )
    (net (code "5") (name "/ADC_OUT1") (class "Default")
      (node (ref "C5") (pin "1") (pinfunction "1_1") (pintype "passive"))
      (node (ref "D6") (pin "1") (pinfunction "C_1") (pintype "passive"))
      (node (ref "R10") (pin "1") (pinfunction "1_1") (pintype "passive"))
      (node (ref "U1") (pin "5") (pinfunction "AN6_5") (pintype "passive"))
    )
    (net (code "6") (name "/ADC_OUT2") (class "Default")
      (node (ref "C1") (pin "1") (pinfunction "1_1") (pintype "passive"))
      (node (ref "D4") (pin "1") (pinfunction "C_1") (pintype "passive"))
      (node (ref "R8") (pin "1") (pinfunction "1_1") (pintype "passive"))
      (node (ref "U1") (pin "7") (pinfunction "AN3_7") (pintype "passive"))
    )
    (net (code "7") (name "/ADC_OUT3") (class "Default")
      (node (ref "C6") (pin "1") (pinfunction "1_1") (pintype "passive"))
      (node (ref "D7") (pin "1") (pinfunction "C_1") (pintype "passive"))
      (node (ref "R11") (pin "1") (pinfunction "1_1") (pintype "passive"))
      (node (ref "U1") (pin "9") (pinfunction "AN5_9") (pintype "passive"))
    )
    (net (code "8") (name "/ADC_OUT4") (class "Default")
      (node (ref "C2") (pin "1") (pinfunction "1_1") (pintype "passive"))
      (node (ref "D5") (pin "1") (pinfunction "C_1") (pintype "passive"))
      (node (ref "R9") (pin "1") (pinfunction "1_1") (pintype "passive"))
      (node (ref "U1") (pin "10") (pinfunction "AN7_10") (pintype "passive"))
    )
    (net (code "9") (name "/ADC_OUT5") (class "Default")
      (node (ref "C9") (pin "1") (pinfunction "1_1") (pintype "passive"))
      (node (ref "D9") (pin "1") (pinfunction "C_1") (pintype "passive"))
      (node (ref "R21") (pin "1") (pinfunction "1_1") (pintype "passive"))
      (node (ref "U1") (pin "11") (pinfunction "AN2_11") (pintype "passive"))
    )
    (net (code "10") (name "/ADC_OUT6") (class "Default")
      (node (ref "C7") (pin "1") (pinfunction "1_1") (pintype "passive"))
      (node (ref "D8") (pin "1") (pinfunction "C_1") (pintype "passive"))
      (node (ref "R20") (pin "1") (pinfunction "1_1") (pintype "passive"))
      (node (ref "U1") (pin "12") (pinfunction "AN4_12") (pintype "passive"))
    )
    (net (code "11") (name "/AN21") (class "Default")
      (node (ref "U1") (pin "2") (pinfunction "AN21_2") (pintype "passive"))
    )
    (net (code "12") (name "/BT_RX") (class "Default")
      (node (ref "R2") (pin "1") (pinfunction "1_1") (pintype "passive"))
      (node (ref "U1") (pin "83") (pinfunction "P11.12_83") (pintype "passive"))
    )
    (net (code "13") (name "/BT_TX") (class "Default")
      (node (ref "R3") (pin "1") (pinfunction "1_1") (pintype "passive"))
      (node (ref "U1") (pin "84") (pinfunction "P11.10_84") (pintype "passive"))
    )
    (net (code "14") (name "/BUZZ") (class "Default")
      (node (ref "R37") (pin "2") (pinfunction "2_2") (pintype "passive"))
      (node (ref "U1") (pin "62") (pinfunction "P15.6_62") (pintype "passive"))
    )
    (net (code "15") (name "/CSI_DAT2") (class "Default")
      (node (ref "J11") (pin "3") (pinfunction "3_3") (pintype "passive"))
      (node (ref "U1") (pin "92") (pinfunction "P02.0_92") (pintype "passive"))
    )
    (net (code "16") (name "/CSI_DAT3") (class "Default")
      (node (ref "J11") (pin "18") (pinfunction "18_18") (pintype "passive"))
      (node (ref "U1") (pin "91") (pinfunction "P02.1_91") (pintype "passive"))
    )
    (net (code "17") (name "/CSI_DAT4") (class "Default")
      (node (ref "J11") (pin "4") (pinfunction "4_4") (pintype "passive"))
      (node (ref "U1") (pin "95") (pinfunction "P02.2_95") (pintype "passive"))
    )
    (net (code "18") (name "/CSI_DAT5") (class "Default")
      (node (ref "J11") (pin "17") (pinfunction "17_17") (pintype "passive"))
      (node (ref "U1") (pin "94") (pinfunction "P02.3_94") (pintype "passive"))
    )
    (net (code "19") (name "/CSI_DAT6") (class "Default")
      (node (ref "J11") (pin "5") (pinfunction "5_5") (pintype "passive"))
      (node (ref "U1") (pin "93") (pinfunction "P02.4_93") (pintype "passive"))
    )
    (net (code "20") (name "/CSI_DAT7") (class "Default")
      (node (ref "J11") (pin "16") (pinfunction "16_16") (pintype "passive"))
      (node (ref "U1") (pin "98") (pinfunction "P02.5_98") (pintype "passive"))
    )
    (net (code "21") (name "/CSI_DAT8") (class "Default")
      (node (ref "J11") (pin "6") (pinfunction "6_6") (pintype "passive"))
      (node (ref "U1") (pin "97") (pinfunction "P02.6_97") (pintype "passive"))
    )
    (net (code "22") (name "/CSI_DAT9") (class "Default")
      (node (ref "J11") (pin "15") (pinfunction "15_15") (pintype "passive"))
      (node (ref "U1") (pin "96") (pinfunction "P02.7_96") (pintype "passive"))
    )
    (net (code "23") (name "/CSI_PIX") (class "Default")
      (node (ref "J11") (pin "8") (pinfunction "8_8") (pintype "passive"))
      (node (ref "U1") (pin "102") (pinfunction "P00.4_102") (pintype "passive"))
    )
    (net (code "24") (name "/CSI_VSYNC") (class "Default")
      (node (ref "J11") (pin "12") (pinfunction "12_12") (pintype "passive"))
      (node (ref "U1") (pin "64") (pinfunction "P15.1_64") (pintype "passive"))
    )
    (net (code "25") (name "/DC_PowerIN") (class "Default")
      (node (ref "JP2") (pin "1") (pinfunction "1_1") (pintype "passive"))
      (node (ref "Q1") (pin "1") (pinfunction "G_1") (pintype "passive"))
      (node (ref "SW1") (pin "3") (pinfunction "NC_3") (pintype "passive"))
    )
    (net (code "26") (name "/EnCode1_Dir") (class "Default")
      (node (ref "J9") (pin "5") (pinfunction "5_5") (pintype "passive"))
      (node (ref "U1") (pin "89") (pinfunction "P10.1_89") (pintype "passive"))
    )
    (net (code "27") (name "/EnCode1_LSB") (class "Default")
      (node (ref "J9") (pin "2") (pinfunction "2_2") (pintype "passive"))
      (node (ref "U1") (pin "88") (pinfunction "P10.3_88") (pintype "passive"))
    )
    (net (code "28") (name "/EnCode2_Dir") (class "Default")
      (node (ref "J10") (pin "5") (pinfunction "5_5") (pintype "passive"))
      (node (ref "U1") (pin "48") (pinfunction "P20.0_48") (pintype "passive"))
    )
    (net (code "29") (name "/EnCode2_LSB") (class "Default")
      (node (ref "J10") (pin "2") (pinfunction "2_2") (pintype "passive"))
      (node (ref "U1") (pin "49") (pinfunction "P20.3_49") (pintype "passive"))
    )
    (net (code "30") (name "/GanHuangGuan") (class "Default")
      (node (ref "J6") (pin "2") (pinfunction "2_2") (pintype "passive"))
      (node (ref "R6") (pin "2") (pinfunction "2_2") (pintype "passive"))
      (node (ref "U1") (pin "110") (pinfunction "P00.8_110") (pintype "passive"))
    )
    (net (code "31") (name "/ICM_CS") (class "Default")
      (node (ref "J4") (pin "6") (pinfunction "6_6") (pintype "passive"))
      (node (ref "U1") (pin "67") (pinfunction "P15.2_67") (pintype "passive"))
    )
    (net (code "32") (name "/ICM_GND") (class "Default")
      (node (ref "J4") (pin "1") (pinfunction "1_1") (pintype "passive"))
    )
    (net (code "33") (name "/ICM_SA0{slash}SDO") (class "Default")
      (node (ref "J4") (pin "5") (pinfunction "5_5") (pintype "passive"))
      (node (ref "U1") (pin "69") (pinfunction "P15.7_69") (pintype "passive"))
    )
    (net (code "34") (name "/ICM_SCL{slash}SPC") (class "Default")
      (node (ref "J4") (pin "3") (pinfunction "3_3") (pintype "passive"))
      (node (ref "U1") (pin "68") (pinfunction "P15.8_68") (pintype "passive"))
    )
    (net (code "35") (name "/ICM_SDA{slash}SDI") (class "Default")
      (node (ref "J4") (pin "4") (pinfunction "4_4") (pintype "passive"))
      (node (ref "U1") (pin "61") (pinfunction "P15.5_61") (pintype "passive"))
    )
    (net (code "36") (name "/IIC_SCL") (class "Default")
      (node (ref "J3") (pin "3") (pinfunction "3_3") (pintype "passive"))
      (node (ref "J7") (pin "6") (pinfunction "6_6") (pintype "passive"))
      (node (ref "U1") (pin "77") (pinfunction "P13.1_77") (pintype "passive"))
    )
    (net (code "37") (name "/IIC_SDA") (class "Default")
      (node (ref "J3") (pin "4") (pinfunction "4_4") (pintype "passive"))
      (node (ref "J7") (pin "5") (pinfunction "5_5") (pintype "passive"))
      (node (ref "U1") (pin "76") (pinfunction "P13.2_76") (pintype "passive"))
    )
    (net (code "38") (name "/KEY1") (class "Default")
      (node (ref "K2") (pin "B") (pinfunction "B_B") (pintype "passive"))
      (node (ref "R33") (pin "1") (pinfunction "1_1") (pintype "passive"))
      (node (ref "U1") (pin "86") (pinfunction "P10.2_86") (pintype "passive"))
    )
    (net (code "39") (name "/KEY2") (class "Default")
      (node (ref "K3") (pin "B") (pinfunction "B_B") (pintype "passive"))
      (node (ref "R34") (pin "1") (pinfunction "1_1") (pintype "passive"))
      (node (ref "U1") (pin "81") (pinfunction "P11.9_81") (pintype "passive"))
    )
    (net (code "40") (name "/KEY3") (class "Default")
      (node (ref "K4") (pin "B") (pinfunction "B_B") (pintype "passive"))
      (node (ref "R35") (pin "1") (pinfunction "1_1") (pintype "passive"))
      (node (ref "U1") (pin "85") (pinfunction "P11.11_85") (pintype "passive"))
    )
    (net (code "41") (name "/KEY4") (class "Default")
      (node (ref "K5") (pin "B") (pinfunction "B_B") (pintype "passive"))
      (node (ref "R36") (pin "1") (pinfunction "1_1") (pintype "passive"))
      (node (ref "U1") (pin "78") (pinfunction "P13.3_78") (pintype "passive"))
    )
    (net (code "42") (name "/KEY5") (class "Default")
      (node (ref "K6") (pin "B") (pinfunction "B_B") (pintype "passive"))
      (node (ref "R32") (pin "1") (pinfunction "1_1") (pintype "passive"))
      (node (ref "U1") (pin "82") (pinfunction "P11.6_82") (pintype "passive"))
    )
    (net (code "43") (name "/LC1") (class "Default")
      (node (ref "J12") (pin "1") (pinfunction "1_1") (pintype "passive"))
      (node (ref "U4") (pin "5") (pinfunction "+IN2_5") (pintype "passive"))
    )
    (net (code "44") (name "/LC2") (class "Default")
      (node (ref "J12") (pin "3") (pinfunction "3_3") (pintype "passive"))
      (node (ref "U4") (pin "3") (pinfunction "+IN1_3") (pintype "passive"))
    )
    (net (code "45") (name "/LC3") (class "Default")
      (node (ref "J13") (pin "1") (pinfunction "1_1") (pintype "passive"))
      (node (ref "U2") (pin "5") (pinfunction "+IN2_5") (pintype "passive"))
    )
    (net (code "46") (name "/LC4") (class "Default")
      (node (ref "J13") (pin "3") (pinfunction "3_3") (pintype "passive"))
      (node (ref "U2") (pin "3") (pinfunction "+IN1_3") (pintype "passive"))
    )
    (net (code "47") (name "/LC5") (class "Default")
      (node (ref "J14") (pin "1") (pinfunction "1_1") (pintype "passive"))
      (node (ref "U3") (pin "5") (pinfunction "+IN2_5") (pintype "passive"))
    )
    (net (code "48") (name "/LC6") (class "Default")
      (node (ref "J14") (pin "3") (pinfunction "3_3") (pintype "passive"))
      (node (ref "U3") (pin "3") (pinfunction "+IN1_3") (pintype "passive"))
    )
    (net (code "49") (name "/P00.2") (class "Default")
      (node (ref "U1") (pin "104") (pinfunction "P00.2_104") (pintype "passive"))
    )
    (net (code "50") (name "/P00.3") (class "Default")
      (node (ref "U1") (pin "103") (pinfunction "P00.3_103") (pintype "passive"))
    )
    (net (code "51") (name "/P00.5") (class "Default")
      (node (ref "U1") (pin "107") (pinfunction "P00.5_107") (pintype "passive"))
    )
    (net (code "52") (name "/P00.6") (class "Default")
      (node (ref "U1") (pin "106") (pinfunction "P00.6_106") (pintype "passive"))
    )
    (net (code "53") (name "/P00.9") (class "Default")
      (node (ref "U1") (pin "109") (pinfunction "P00.9_109") (pintype "passive"))
    )
    (net (code "54") (name "/P02.8") (class "Default")
      (node (ref "U1") (pin "101") (pinfunction "P02.8_101") (pintype "passive"))
    )
    (net (code "55") (name "/P11.2") (class "Default")
      (node (ref "J11") (pin "14") (pinfunction "14_14") (pintype "passive"))
      (node (ref "U1") (pin "79") (pinfunction "P11.2_79") (pintype "passive"))
    )
    (net (code "56") (name "/P11.3") (class "Default")
      (node (ref "J11") (pin "7") (pinfunction "7_7") (pintype "passive"))
      (node (ref "U1") (pin "80") (pinfunction "P11.3_80") (pintype "passive"))
    )
    (net (code "57") (name "/P14.0{slash}TX") (class "Default")
      (node (ref "J2") (pin "4") (pinfunction "4_4") (pintype "passive"))
      (node (ref "U1") (pin "37") (pinfunction "P14.0/TX_37") (pintype "passive"))
    )
    (net (code "58") (name "/P14.1{slash}RX") (class "Default")
      (node (ref "J2") (pin "5") (pinfunction "5_5") (pintype "passive"))
      (node (ref "U1") (pin "34") (pinfunction "P14.1/RX_34") (pintype "passive"))
    )
    (net (code "59") (name "/PORST") (class "Default")
      (node (ref "J2") (pin "6") (pinfunction "6_6") (pintype "passive"))
      (node (ref "K1") (pin "A") (pinfunction "A_A") (pintype "passive"))
      (node (ref "U1") (pin "33") (pinfunction "PORST_33") (pintype "passive"))
    )
    (net (code "60") (name "/PWM_Motor1+") (class "Default")
      (node (ref "J") (pin "5") (pinfunction "5_5") (pintype "passive"))
      (node (ref "JP1") (pin "4") (pinfunction "4_4") (pintype "passive"))
      (node (ref "U1") (pin "24") (pinfunction "P32.4_24") (pintype "passive"))
    )
    (net (code "61") (name "/PWM_Motor1-") (class "Default")
      (node (ref "J") (pin "4") (pinfunction "4_4") (pintype "passive"))
      (node (ref "JP1") (pin "5") (pinfunction "5_5") (pintype "passive"))
      (node (ref "U1") (pin "29") (pinfunction "P23.1_29") (pintype "passive"))
    )
    (net (code "62") (name "/PWM_Motor2+") (class "Default")
      (node (ref "J") (pin "3") (pinfunction "3_3") (pintype "passive"))
      (node (ref "JP1") (pin "6") (pinfunction "6_6") (pintype "passive"))
      (node (ref "U1") (pin "32") (pinfunction "P22.3_32") (pintype "passive"))
    )
    (net (code "63") (name "/PWM_Motor2-") (class "Default")
      (node (ref "J") (pin "2") (pinfunction "2_2") (pintype "passive"))
      (node (ref "JP1") (pin "7") (pinfunction "7_7") (pintype "passive"))
      (node (ref "U1") (pin "35") (pinfunction "P21.2_35") (pintype "passive"))
    )
    (net (code "64") (name "/PWM_ServoMotor") (class "Default")
      (node (ref "D3") (pin "1") (pinfunction "C_1") (pintype "passive"))
      (node (ref "R7") (pin "1") (pinfunction "1_1") (pintype "passive"))
      (node (ref "U1") (pin "54") (pinfunction "P20.8_54") (pintype "passive"))
    )
    (net (code "65") (name "/SW1") (class "Default")
      (node (ref "RN1") (pin "4") (pinfunction "4_4") (pintype "passive"))
      (node (ref "SW2") (pin "1") (pinfunction "1_1") (pintype "passive"))
      (node (ref "U1") (pin "22") (pinfunction "P33.11_22") (pintype "passive"))
    )
    (net (code "66") (name "/SW2") (class "Default")
      (node (ref "RN1") (pin "3") (pinfunction "3_3") (pintype "passive"))
      (node (ref "SW2") (pin "2") (pinfunction "2_2") (pintype "passive"))
      (node (ref "U1") (pin "20") (pinfunction "P33.9_20") (pintype "passive"))
    )
    (net (code "67") (name "/SW3") (class "Default")
      (node (ref "RN1") (pin "2") (pinfunction "2_2") (pintype "passive"))
      (node (ref "SW2") (pin "3") (pinfunction "3_3") (pintype "passive"))
      (node (ref "U1") (pin "19") (pinfunction "P33.7_19") (pintype "passive"))
    )
    (net (code "68") (name "/SW4") (class "Default")
      (node (ref "RN1") (pin "1") (pinfunction "1_1") (pintype "passive"))
      (node (ref "SW2") (pin "4") (pinfunction "4_4") (pintype "passive"))
      (node (ref "U1") (pin "17") (pinfunction "P33.6_17") (pintype "passive"))
    )
    (net (code "69") (name "/TCK") (class "Default")
      (node (ref "J2") (pin "9") (pinfunction "9_9") (pintype "passive"))
      (node (ref "U1") (pin "42") (pinfunction "TCK_42") (pintype "passive"))
    )
    (net (code "70") (name "/TDO{slash}P21.7") (class "Default")
      (node (ref "J2") (pin "8") (pinfunction "8_8") (pintype "passive"))
      (node (ref "U1") (pin "39") (pinfunction "TDO/P21.7_39") (pintype "passive"))
    )
    (net (code "71") (name "/TFT_CS") (class "Default")
      (node (ref "LCD1") (pin "3") (pinfunction "CS_3") (pintype "passive"))
      (node (ref "U1") (pin "60") (pinfunction "P20.14_60") (pintype "passive"))
    )
    (net (code "72") (name "/TFT_D{slash}C") (class "Default")
      (node (ref "LCD1") (pin "6") (pinfunction "D/C_6") (pintype "passive"))
      (node (ref "U1") (pin "58") (pinfunction "P20.12_58") (pintype "passive"))
    )
    (net (code "73") (name "/TFT_RST") (class "Default")
      (node (ref "LCD1") (pin "7") (pinfunction "RST_7") (pintype "passive"))
      (node (ref "U1") (pin "59") (pinfunction "P20.13_59") (pintype "passive"))
    )
    (net (code "74") (name "/TFT_SCK") (class "Default")
      (node (ref "LCD1") (pin "4") (pinfunction "SCK_4") (pintype "passive"))
      (node (ref "U1") (pin "57") (pinfunction "P20.11_57") (pintype "passive"))
    )
    (net (code "75") (name "/TFT_SDI") (class "Default")
      (node (ref "LCD1") (pin "5") (pinfunction "SDI_5") (pintype "passive"))
      (node (ref "U1") (pin "56") (pinfunction "P20.10_56") (pintype "passive"))
    )
    (net (code "76") (name "/TMS") (class "Default")
      (node (ref "J2") (pin "10") (pinfunction "10_10") (pintype "passive"))
      (node (ref "U1") (pin "45") (pinfunction "TMS_45") (pintype "passive"))
    )
    (net (code "77") (name "/TOF_RXD") (class "Default")
      (node (ref "J7") (pin "3") (pinfunction "3_3") (pintype "passive"))
      (node (ref "U1") (pin "100") (pinfunction "P00.0_100") (pintype "passive"))
    )
    (net (code "78") (name "/TOF_TXD") (class "Default")
      (node (ref "J7") (pin "4") (pinfunction "4_4") (pintype "passive"))
      (node (ref "U1") (pin "99") (pinfunction "P00.1_99") (pintype "passive"))
    )
    (net (code "79") (name "/TRST") (class "Default")
      (node (ref "J2") (pin "7") (pinfunction "7_7") (pintype "passive"))
      (node (ref "U1") (pin "36") (pinfunction "TRST_36") (pintype "passive"))
    )
    (net (code "80") (name "/VCC_ServoMotor") (class "Default")
      (node (ref "C10") (pin "1") (pinfunction "1_1") (pintype "passive"))
      (node (ref "J8") (pin "2") (pinfunction "2_2") (pintype "passive"))
      (node (ref "L1") (pin "2") (pinfunction "2_2") (pintype "passive"))
      (node (ref "R28") (pin "1") (pinfunction "1_1") (pintype "passive"))
    )
    (net (code "81") (name "/VEE") (class "Default")
      (node (ref "JP2") (pin "2") (pinfunction "2_2") (pintype "passive"))
      (node (ref "Q1") (pin "4") (pinfunction "D_4") (pintype "passive"))
    )
    (net (code "82") (name "7.2V") (class "Default")
      (node (ref "C11") (pin "1") (pinfunction "1_1") (pintype "passive"))
      (node (ref "C14") (pin "1") (pinfunction "1_1") (pintype "passive"))
      (node (ref "C15") (pin "1") (pinfunction "1_1") (pintype "passive"))
      (node (ref "F1") (pin "2") (pinfunction "2_2") (pintype "passive"))
      (node (ref "R29") (pin "1") (pinfunction "1_1") (pintype "passive"))
      (node (ref "R30") (pin "2") (pinfunction "2_2") (pintype "passive"))
      (node (ref "R31") (pin "1") (pinfunction "1_1") (pintype "passive"))
      (node (ref "U5") (pin "4") (pinfunction "IN_4") (pintype "passive"))
      (node (ref "U7") (pin "1") (pinfunction "VIN_1") (pintype "passive"))
    )
    (net (code "83") (name "AGND") (class "Default")
      (node (ref "C1") (pin "2") (pinfunction "2_2") (pintype "passive"))
      (node (ref "C2") (pin "2") (pinfunction "2_2") (pintype "passive"))
      (node (ref "C3") (pin "2") (pinfunction "2_2") (pintype "passive"))
      (node (ref "C4") (pin "2") (pinfunction "2_2") (pintype "passive"))
      (node (ref "C5") (pin "2") (pinfunction "2_2") (pintype "passive"))
      (node (ref "C6") (pin "2") (pinfunction "2_2") (pintype "passive"))
      (node (ref "C7") (pin "2") (pinfunction "2_2") (pintype "passive"))
      (node (ref "C8") (pin "2") (pinfunction "2_2") (pintype "passive"))
      (node (ref "C9") (pin "2") (pinfunction "2_2") (pintype "passive"))
      (node (ref "D4") (pin "2") (pinfunction "A_2") (pintype "passive"))
      (node (ref "D5") (pin "2") (pinfunction "A_2") (pintype "passive"))
      (node (ref "D6") (pin "2") (pinfunction "A_2") (pintype "passive"))
      (node (ref "D7") (pin "2") (pinfunction "A_2") (pintype "passive"))
      (node (ref "D8") (pin "2") (pinfunction "A_2") (pintype "passive"))
      (node (ref "D9") (pin "2") (pinfunction "A_2") (pintype "passive"))
      (node (ref "J12") (pin "2") (pinfunction "2_2") (pintype "passive"))
      (node (ref "J13") (pin "2") (pinfunction "2_2") (pintype "passive"))
      (node (ref "J14") (pin "2") (pinfunction "2_2") (pintype "passive"))
      (node (ref "R16") (pin "1") (pinfunction "1_1") (pintype "passive"))
      (node (ref "R17") (pin "1") (pinfunction "1_1") (pintype "passive"))
      (node (ref "R18") (pin "2") (pinfunction "2_2") (pintype "passive"))
      (node (ref "R19") (pin "2") (pinfunction "2_2") (pintype "passive"))
      (node (ref "R24") (pin "1") (pinfunction "1_1") (pintype "passive"))
      (node (ref "R25") (pin "2") (pinfunction "2_2") (pintype "passive"))
      (node (ref "R26") (pin "1") (pinfunction "1_1") (pintype "passive"))
      (node (ref "U2") (pin "4") (pinfunction "GND_4") (pintype "passive"))
      (node (ref "U3") (pin "4") (pinfunction "GND_4") (pintype "passive"))
      (node (ref "U4") (pin "4") (pinfunction "GND_4") (pintype "passive"))
    )
    (net (code "84") (name "GND") (class "Default")
      (node (ref "C10") (pin "2") (pinfunction "2_2") (pintype "passive"))
      (node (ref "C11") (pin "2") (pinfunction "2_2") (pintype "passive"))
      (node (ref "C12") (pin "2") (pinfunction "2_2") (pintype "passive"))
      (node (ref "C13") (pin "2") (pinfunction "2_2") (pintype "passive"))
      (node (ref "C14") (pin "2") (pinfunction "2_2") (pintype "passive"))
      (node (ref "C15") (pin "2") (pinfunction "2_2") (pintype "passive"))
      (node (ref "C16") (pin "2") (pinfunction "2_2") (pintype "passive"))
      (node (ref "C17") (pin "1") (pinfunction "1_1") (pintype "passive"))
      (node (ref "C18") (pin "2") (pinfunction "2_2") (pintype "passive"))
      (node (ref "D1") (pin "2") (pinfunction "A_2") (pintype "passive"))
      (node (ref "D10") (pin "1") (pinfunction "A_1") (pintype "passive"))
      (node (ref "D11") (pin "C") (pinfunction "C_C") (pintype "passive"))
      (node (ref "D13") (pin "1") (pinfunction "A_1") (pintype "passive"))
      (node (ref "D2") (pin "2") (pinfunction "A_2") (pintype "passive"))
      (node (ref "D3") (pin "2") (pinfunction "A_2") (pintype "passive"))
      (node (ref "J") (pin "1") (pinfunction "1_1") (pintype "passive"))
      (node (ref "J1") (pin "2") (pinfunction "2_2") (pintype "passive"))
      (node (ref "J10") (pin "1") (pinfunction "1_1") (pintype "passive"))
      (node (ref "J11") (pin "11") (pinfunction "11_11") (pintype "passive"))
      (node (ref "J11") (pin "9") (pinfunction "9_9") (pintype "passive"))
      (node (ref "J2") (pin "2") (pinfunction "2_2") (pintype "passive"))
      (node (ref "J2") (pin "3") (pinfunction "3_3") (pintype "passive"))
      (node (ref "J3") (pin "2") (pinfunction "2_2") (pintype "passive"))
      (node (ref "J6") (pin "1") (pinfunction "1_1") (pintype "passive"))
      (node (ref "J7") (pin "1") (pinfunction "1_1") (pintype "passive"))
      (node (ref "J8") (pin "1") (pinfunction "1_1") (pintype "passive"))
      (node (ref "J9") (pin "1") (pinfunction "1_1") (pintype "passive"))
      (node (ref "JP1") (pin "8") (pinfunction "8_8") (pintype "passive"))
      (node (ref "K1") (pin "B") (pinfunction "B_B") (pintype "passive"))
      (node (ref "K2") (pin "A") (pinfunction "A_A") (pintype "passive"))
      (node (ref "K3") (pin "A") (pinfunction "A_A") (pintype "passive"))
      (node (ref "K4") (pin "A") (pinfunction "A_A") (pintype "passive"))
      (node (ref "K5") (pin "A") (pinfunction "A_A") (pintype "passive"))
      (node (ref "K6") (pin "A") (pinfunction "A_A") (pintype "passive"))
      (node (ref "LCD1") (pin "1") (pinfunction "GND_1") (pintype "passive"))
      (node (ref "Q1") (pin "3") (pinfunction "S_3") (pintype "passive"))
      (node (ref "Q2") (pin "2") (pinfunction "E_2") (pintype "passive"))
      (node (ref "R26") (pin "2") (pinfunction "2_2") (pintype "passive"))
      (node (ref "R27") (pin "1") (pinfunction "1_1") (pintype "passive"))
      (node (ref "R39") (pin "2") (pinfunction "2_2") (pintype "passive"))
      (node (ref "R41") (pin "1") (pinfunction "1_1") (pintype "passive"))
      (node (ref "SW2") (pin "5") (pinfunction "5_5") (pintype "passive"))
      (node (ref "SW2") (pin "6") (pinfunction "6_6") (pintype "passive"))
      (node (ref "SW2") (pin "7") (pinfunction "7_7") (pintype "passive"))
      (node (ref "SW2") (pin "8") (pinfunction "8_8") (pintype "passive"))
      (node (ref "U1") (pin "40") (pinfunction "GND_40") (pintype "passive"))
      (node (ref "U1") (pin "43") (pinfunction "GND_43") (pintype "passive"))
      (node (ref "U5") (pin "7") (pinfunction "GND_7") (pintype "passive"))
      (node (ref "U5") (pin "8") (pinfunction "GND_8") (pintype "passive"))
      (node (ref "U6") (pin "1") (pinfunction "GND_1") (pintype "passive"))
      (node (ref "U7") (pin "3") (pinfunction "GND_3") (pintype "passive"))
      (node (ref "U7") (pin "5") (pinfunction "ON#/OFF_5") (pintype "passive"))
      (node (ref "U7") (pin "6") (pinfunction "GND_6") (pintype "passive"))
      (node (ref "U8") (pin "1") (pinfunction "GND_1") (pintype "passive"))
      (node (ref "U8") (pin "2") (pinfunction "EN_2") (pintype "passive"))
    )
    (net (code "85") (name "Net-(C19-Pad2)") (class "Default")
      (node (ref "C19") (pin "2") (pinfunction "2_2") (pintype "passive"))
      (node (ref "R41") (pin "2") (pinfunction "2_2") (pintype "passive"))
    )
    (net (code "86") (name "Net-(D10-C)") (class "Default")
      (node (ref "D10") (pin "2") (pinfunction "C_2") (pintype "passive"))
      (node (ref "L1") (pin "1") (pinfunction "1_1") (pintype "passive"))
      (node (ref "U5") (pin "5") (pinfunction "SW_5") (pintype "passive"))
      (node (ref "U5") (pin "6") (pinfunction "SW_6") (pintype "passive"))
    )
    (net (code "87") (name "Net-(D11-PadA)") (class "Default")
      (node (ref "D11") (pin "A") (pinfunction "A_A") (pintype "passive"))
      (node (ref "R30") (pin "1") (pinfunction "1_1") (pintype "passive"))
    )
    (net (code "88") (name "Net-(D12-C)") (class "Default")
      (node (ref "C17") (pin "2") (pinfunction "2_2") (pintype "passive"))
      (node (ref "D12") (pin "2") (pinfunction "C_2") (pintype "passive"))
      (node (ref "U8") (pin "3") (pinfunction "IN/2_3") (pintype "passive"))
      (node (ref "U8") (pin "4") (pinfunction "IN_4") (pintype "passive"))
    )
    (net (code "89") (name "Net-(D13-C)") (class "Default")
      (node (ref "D13") (pin "2") (pinfunction "C_2") (pintype "passive"))
      (node (ref "L2") (pin "2") (pinfunction "2_2") (pintype "passive"))
      (node (ref "U7") (pin "2") (pinfunction "OUTPUT_2") (pintype "passive"))
    )
    (net (code "90") (name "Net-(FM1-－)") (class "Default")
      (node (ref "FM1") (pin "2") (pinfunction "－_2") (pintype "passive"))
      (node (ref "Q2") (pin "3") (pinfunction "C_3") (pintype "passive"))
    )
    (net (code "91") (name "Net-(J1-Pad3)") (class "Default")
      (node (ref "J1") (pin "3") (pinfunction "3_3") (pintype "passive"))
      (node (ref "R3") (pin "2") (pinfunction "2_2") (pintype "passive"))
    )
    (net (code "92") (name "Net-(J1-Pad4)") (class "Default")
      (node (ref "J1") (pin "4") (pinfunction "4_4") (pintype "passive"))
      (node (ref "R2") (pin "2") (pinfunction "2_2") (pintype "passive"))
    )
    (net (code "93") (name "Net-(J8-Pad3)") (class "Default")
      (node (ref "J8") (pin "3") (pinfunction "3_3") (pintype "passive"))
      (node (ref "R7") (pin "2") (pinfunction "2_2") (pintype "passive"))
    )
    (net (code "94") (name "Net-(LCD1-3.3V)") (class "Default")
      (node (ref "LCD1") (pin "2") (pinfunction "3.3V_2") (pintype "passive"))
      (node (ref "R1") (pin "2") (pinfunction "2_2") (pintype "passive"))
    )
    (net (code "95") (name "Net-(Q2-B)") (class "Default")
      (node (ref "Q2") (pin "1") (pinfunction "B_1") (pintype "passive"))
      (node (ref "R37") (pin "1") (pinfunction "1_1") (pintype "passive"))
      (node (ref "R39") (pin "1") (pinfunction "1_1") (pintype "passive"))
    )
    (net (code "96") (name "Net-(SW1-C)") (class "Default")
      (node (ref "F1") (pin "1") (pinfunction "1_1") (pintype "passive"))
      (node (ref "SW1") (pin "2") (pinfunction "C_2") (pintype "passive"))
    )
    (net (code "97") (name "Net-(U2--IN1)") (class "Default")
      (node (ref "R12") (pin "3") (pinfunction "3_3") (pintype "passive"))
      (node (ref "R18") (pin "1") (pinfunction "1_1") (pintype "passive"))
      (node (ref "U2") (pin "2") (pinfunction "-IN1_2") (pintype "passive"))
    )
    (net (code "98") (name "Net-(U2--IN2)") (class "Default")
      (node (ref "R14") (pin "1") (pinfunction "1_1") (pintype "passive"))
      (node (ref "R16") (pin "2") (pinfunction "2_2") (pintype "passive"))
      (node (ref "U2") (pin "6") (pinfunction "-IN2_6") (pintype "passive"))
    )
    (net (code "99") (name "Net-(U2-OUT1)") (class "Default")
      (node (ref "R12") (pin "2") (pinfunction "2_2") (pintype "passive"))
      (node (ref "R8") (pin "2") (pinfunction "2_2") (pintype "passive"))
      (node (ref "U2") (pin "1") (pinfunction "OUT1_1") (pintype "passive"))
    )
    (net (code "100") (name "Net-(U2-OUT2)") (class "Default")
      (node (ref "R10") (pin "2") (pinfunction "2_2") (pintype "passive"))
      (node (ref "R14") (pin "2") (pinfunction "2_2") (pintype "passive"))
      (node (ref "U2") (pin "7") (pinfunction "OUT2_7") (pintype "passive"))
    )
    (net (code "101") (name "Net-(U3--IN1)") (class "Default")
      (node (ref "R13") (pin "3") (pinfunction "3_3") (pintype "passive"))
      (node (ref "R19") (pin "1") (pinfunction "1_1") (pintype "passive"))
      (node (ref "U3") (pin "2") (pinfunction "-IN1_2") (pintype "passive"))
    )
    (net (code "102") (name "Net-(U3--IN2)") (class "Default")
      (node (ref "R15") (pin "1") (pinfunction "1_1") (pintype "passive"))
      (node (ref "R17") (pin "2") (pinfunction "2_2") (pintype "passive"))
      (node (ref "U3") (pin "6") (pinfunction "-IN2_6") (pintype "passive"))
    )
    (net (code "103") (name "Net-(U3-OUT1)") (class "Default")
      (node (ref "R13") (pin "2") (pinfunction "2_2") (pintype "passive"))
      (node (ref "R9") (pin "2") (pinfunction "2_2") (pintype "passive"))
      (node (ref "U3") (pin "1") (pinfunction "OUT1_1") (pintype "passive"))
    )
    (net (code "104") (name "Net-(U3-OUT2)") (class "Default")
      (node (ref "R11") (pin "2") (pinfunction "2_2") (pintype "passive"))
      (node (ref "R15") (pin "2") (pinfunction "2_2") (pintype "passive"))
      (node (ref "U3") (pin "7") (pinfunction "OUT2_7") (pintype "passive"))
    )
    (net (code "105") (name "Net-(U4--IN1)") (class "Default")
      (node (ref "R22") (pin "3") (pinfunction "3_3") (pintype "passive"))
      (node (ref "R25") (pin "1") (pinfunction "1_1") (pintype "passive"))
      (node (ref "U4") (pin "2") (pinfunction "-IN1_2") (pintype "passive"))
    )
    (net (code "106") (name "Net-(U4--IN2)") (class "Default")
      (node (ref "R23") (pin "1") (pinfunction "1_1") (pintype "passive"))
      (node (ref "R24") (pin "2") (pinfunction "2_2") (pintype "passive"))
      (node (ref "U4") (pin "6") (pinfunction "-IN2_6") (pintype "passive"))
    )
    (net (code "107") (name "Net-(U4-OUT1)") (class "Default")
      (node (ref "R20") (pin "2") (pinfunction "2_2") (pintype "passive"))
      (node (ref "R22") (pin "2") (pinfunction "2_2") (pintype "passive"))
      (node (ref "U4") (pin "1") (pinfunction "OUT1_1") (pintype "passive"))
    )
    (net (code "108") (name "Net-(U4-OUT2)") (class "Default")
      (node (ref "R21") (pin "2") (pinfunction "2_2") (pintype "passive"))
      (node (ref "R23") (pin "2") (pinfunction "2_2") (pintype "passive"))
      (node (ref "U4") (pin "7") (pinfunction "OUT2_7") (pintype "passive"))
    )
    (net (code "109") (name "Net-(U5-EN)") (class "Default")
      (node (ref "R29") (pin "2") (pinfunction "2_2") (pintype "passive"))
      (node (ref "U5") (pin "2") (pinfunction "EN_2") (pintype "passive"))
    )
    (net (code "110") (name "Net-(U5-FB)") (class "Default")
      (node (ref "R27") (pin "2") (pinfunction "2_2") (pintype "passive"))
      (node (ref "R28") (pin "2") (pinfunction "2_2") (pintype "passive"))
      (node (ref "U5") (pin "1") (pinfunction "FB_1") (pintype "passive"))
    )
    (net (code "111") (name "Net-(U5-OCSET)") (class "Default")
      (node (ref "R31") (pin "2") (pinfunction "2_2") (pintype "passive"))
      (node (ref "U5") (pin "3") (pinfunction "OCSET_3") (pintype "passive"))
    )
    (net (code "112") (name "Net-(U7-FB)") (class "Default")
      (node (ref "C16") (pin "1") (pinfunction "1_1") (pintype "passive"))
      (node (ref "F2") (pin "1") (pinfunction "1_1") (pintype "passive"))
      (node (ref "L2") (pin "1") (pinfunction "1_1") (pintype "passive"))
      (node (ref "U7") (pin "4") (pinfunction "FB_4") (pintype "passive"))
    )
    (net (code "113") (name "Net-(U8-OUT)") (class "Default")
      (node (ref "C18") (pin "1") (pinfunction "1_1") (pintype "passive"))
      (node (ref "C19") (pin "1") (pinfunction "1_1") (pintype "passive"))
      (node (ref "R38") (pin "1") (pinfunction "1_1") (pintype "passive"))
      (node (ref "R40") (pin "2") (pinfunction "2_2") (pintype "passive"))
      (node (ref "U8") (pin "5") (pinfunction "OUT/2_5") (pintype "passive"))
      (node (ref "U8") (pin "6") (pinfunction "OUT_6") (pintype "passive"))
      (node (ref "U8") (pin "7") (pinfunction "SENSEFB_7") (pintype "passive"))
    )
    (net (code "114") (name "Net-(U8-RESET)") (class "Default")
      (node (ref "R40") (pin "1") (pinfunction "1_1") (pintype "passive"))
      (node (ref "U8") (pin "8") (pinfunction "RESET_8") (pintype "passive"))
    )
    (net (code "115") (name "VCC3.3_MCU") (class "Default")
      (node (ref "J2") (pin "1") (pinfunction "1_1") (pintype "passive"))
      (node (ref "R38") (pin "2") (pinfunction "2_2") (pintype "passive"))
      (node (ref "U1") (pin "46") (pinfunction "3V3_46") (pintype "passive"))
    )
    (net (code "116") (name "VCC_3.3V") (class "Default")
      (node (ref "C13") (pin "1") (pinfunction "1_1") (pintype "passive"))
      (node (ref "FM1") (pin "1") (pinfunction "+_1") (pintype "passive"))
      (node (ref "J11") (pin "10") (pinfunction "10_10") (pintype "passive"))
      (node (ref "J3") (pin "1") (pinfunction "1_1") (pintype "passive"))
      (node (ref "J7") (pin "2") (pinfunction "2_2") (pintype "passive"))
      (node (ref "R1") (pin "1") (pinfunction "1_1") (pintype "passive"))
      (node (ref "R32") (pin "2") (pinfunction "2_2") (pintype "passive"))
      (node (ref "R33") (pin "2") (pinfunction "2_2") (pintype "passive"))
      (node (ref "R34") (pin "2") (pinfunction "2_2") (pintype "passive"))
      (node (ref "R35") (pin "2") (pinfunction "2_2") (pintype "passive"))
      (node (ref "R36") (pin "2") (pinfunction "2_2") (pintype "passive"))
      (node (ref "R6") (pin "1") (pinfunction "1_1") (pintype "passive"))
      (node (ref "RN1") (pin "5") (pinfunction "5_5") (pintype "passive"))
      (node (ref "RN1") (pin "6") (pinfunction "6_6") (pintype "passive"))
      (node (ref "RN1") (pin "7") (pinfunction "7_7") (pintype "passive"))
      (node (ref "RN1") (pin "8") (pinfunction "8_8") (pintype "passive"))
      (node (ref "U6") (pin "2") (pinfunction "Out_2") (pintype "passive"))
      (node (ref "U6") (pin "4") (pinfunction "TAB_4") (pintype "passive"))
    )
    (net (code "117") (name "VCC_5V") (class "Default")
      (node (ref "C12") (pin "1") (pinfunction "1_1") (pintype "passive"))
      (node (ref "C3") (pin "1") (pinfunction "1_1") (pintype "passive"))
      (node (ref "C4") (pin "1") (pinfunction "1_1") (pintype "passive"))
      (node (ref "C8") (pin "1") (pinfunction "1_1") (pintype "passive"))
      (node (ref "D12") (pin "1") (pinfunction "A_1") (pintype "passive"))
      (node (ref "F2") (pin "2") (pinfunction "2_2") (pintype "passive"))
      (node (ref "J1") (pin "1") (pinfunction "1_1") (pintype "passive"))
      (node (ref "J10") (pin "6") (pinfunction "6_6") (pintype "passive"))
      (node (ref "J4") (pin "2") (pinfunction "2_2") (pintype "passive"))
      (node (ref "J9") (pin "6") (pinfunction "6_6") (pintype "passive"))
      (node (ref "U2") (pin "8") (pinfunction "VCC+_8") (pintype "passive"))
      (node (ref "U3") (pin "8") (pinfunction "VCC+_8") (pintype "passive"))
      (node (ref "U4") (pin "8") (pinfunction "VCC+_8") (pintype "passive"))
      (node (ref "U6") (pin "3") (pinfunction "In_3") (pintype "passive"))
    )
    (net (code "118") (name "unconnected-(J-Pad6)") (class "Default")
      (node (ref "J") (pin "6") (pinfunction "6_6") (pintype "passive"))
    )
    (net (code "119") (name "unconnected-(J9-Pad3)") (class "Default")
      (node (ref "J9") (pin "3") (pinfunction "3_3") (pintype "passive"))
    )
    (net (code "120") (name "unconnected-(J9-Pad4)") (class "Default")
      (node (ref "J9") (pin "4") (pinfunction "4_4") (pintype "passive"))
    )
    (net (code "121") (name "unconnected-(J10-Pad3)") (class "Default")
      (node (ref "J10") (pin "3") (pinfunction "3_3") (pintype "passive"))
    )
    (net (code "122") (name "unconnected-(J10-Pad4)") (class "Default")
      (node (ref "J10") (pin "4") (pinfunction "4_4") (pintype "passive"))
    )
    (net (code "123") (name "unconnected-(J11-Pad1)") (class "Default")
      (node (ref "J11") (pin "1") (pinfunction "1_1") (pintype "passive"))
    )
    (net (code "124") (name "unconnected-(J11-Pad2)") (class "Default")
      (node (ref "J11") (pin "2") (pinfunction "2_2") (pintype "passive"))
    )
    (net (code "125") (name "unconnected-(J11-Pad13)") (class "Default")
      (node (ref "J11") (pin "13") (pinfunction "13_13") (pintype "passive"))
    )
    (net (code "126") (name "unconnected-(J11-Pad19)") (class "Default")
      (node (ref "J11") (pin "19") (pinfunction "19_19") (pintype "passive"))
    )
    (net (code "127") (name "unconnected-(J11-Pad20)") (class "Default")
      (node (ref "J11") (pin "20") (pinfunction "20_20") (pintype "passive"))
    )
    (net (code "128") (name "unconnected-(JP1-Pad3)") (class "Default")
      (node (ref "JP1") (pin "3") (pinfunction "3_3") (pintype "passive"))
    )
    (net (code "129") (name "unconnected-(R12-Pad1)") (class "Default")
      (node (ref "R12") (pin "1") (pinfunction "1_1") (pintype "passive"))
    )
    (net (code "130") (name "unconnected-(R13-Pad1)") (class "Default")
      (node (ref "R13") (pin "1") (pinfunction "1_1") (pintype "passive"))
    )
    (net (code "131") (name "unconnected-(R14-Pad3)") (class "Default")
      (node (ref "R14") (pin "3") (pinfunction "3_3") (pintype "passive"))
    )
    (net (code "132") (name "unconnected-(R15-Pad3)") (class "Default")
      (node (ref "R15") (pin "3") (pinfunction "3_3") (pintype "passive"))
    )
    (net (code "133") (name "unconnected-(R22-Pad1)") (class "Default")
      (node (ref "R22") (pin "1") (pinfunction "1_1") (pintype "passive"))
    )
    (net (code "134") (name "unconnected-(R23-Pad3)") (class "Default")
      (node (ref "R23") (pin "3") (pinfunction "3_3") (pintype "passive"))
    )
    (net (code "135") (name "unconnected-(R27-Pad3)") (class "Default")
      (node (ref "R27") (pin "3") (pinfunction "3_3") (pintype "passive"))
    )
    (net (code "136") (name "unconnected-(SW1-ON-Pad1)") (class "Default")
      (node (ref "SW1") (pin "1") (pinfunction "ON_1") (pintype "passive"))
    )
    (net (code "137") (name "unconnected-(U1A-AN24-Pad125)") (class "Default")
      (node (ref "U1") (pin "125") (pinfunction "AN24_125") (pintype "passive"))
    )
    (net (code "138") (name "unconnected-(U1A-AN36-Pad122)") (class "Default")
      (node (ref "U1") (pin "122") (pinfunction "AN36_122") (pintype "passive"))
    )
    (net (code "139") (name "unconnected-(U1A-AN39-Pad119)") (class "Default")
      (node (ref "U1") (pin "119") (pinfunction "AN39_119") (pintype "passive"))
    )
    (net (code "140") (name "unconnected-(U1A-AN46-Pad116)") (class "Default")
      (node (ref "U1") (pin "116") (pinfunction "AN46_116") (pintype "passive"))
    )
    (net (code "141") (name "unconnected-(U1A-AN49-Pad113)") (class "Default")
      (node (ref "U1") (pin "113") (pinfunction "AN49_113") (pintype "passive"))
    )
    (net (code "142") (name "unconnected-(U1B-AN13-Pad126)") (class "Default")
      (node (ref "U1") (pin "126") (pinfunction "AN13_126") (pintype "passive"))
    )
    (net (code "143") (name "unconnected-(U1B-AN16-Pad124)") (class "Default")
      (node (ref "U1") (pin "124") (pinfunction "AN16_124") (pintype "passive"))
    )
    (net (code "144") (name "unconnected-(U1B-AN17-Pad123)") (class "Default")
      (node (ref "U1") (pin "123") (pinfunction "AN17_123") (pintype "passive"))
    )
    (net (code "145") (name "unconnected-(U1B-AN20-Pad127)") (class "Default")
      (node (ref "U1") (pin "127") (pinfunction "AN20_127") (pintype "passive"))
    )
    (net (code "146") (name "unconnected-(U1B-AN25-Pad120)") (class "Default")
      (node (ref "U1") (pin "120") (pinfunction "AN25_120") (pintype "passive"))
    )
    (net (code "147") (name "unconnected-(U1B-AN35-Pad121)") (class "Default")
      (node (ref "U1") (pin "121") (pinfunction "AN35_121") (pintype "passive"))
    )
    (net (code "148") (name "unconnected-(U1B-AN37-Pad117)") (class "Default")
      (node (ref "U1") (pin "117") (pinfunction "AN37_117") (pintype "passive"))
    )
    (net (code "149") (name "unconnected-(U1B-AN38-Pad118)") (class "Default")
      (node (ref "U1") (pin "118") (pinfunction "AN38_118") (pintype "passive"))
    )
    (net (code "150") (name "unconnected-(U1B-AN44-Pad114)") (class "Default")
      (node (ref "U1") (pin "114") (pinfunction "AN44_114") (pintype "passive"))
    )
    (net (code "151") (name "unconnected-(U1B-AN45-Pad115)") (class "Default")
      (node (ref "U1") (pin "115") (pinfunction "AN45_115") (pintype "passive"))
    )
    (net (code "152") (name "unconnected-(U1B-AN47-Pad111)") (class "Default")
      (node (ref "U1") (pin "111") (pinfunction "AN47_111") (pintype "passive"))
    )
    (net (code "153") (name "unconnected-(U1B-AN48-Pad112)") (class "Default")
      (node (ref "U1") (pin "112") (pinfunction "AN48_112") (pintype "passive"))
    )
    (net (code "154") (name "unconnected-(U1B-P00.7-Pad105)") (class "Default")
      (node (ref "U1") (pin "105") (pinfunction "P00.7_105") (pintype "passive"))
    )
    (net (code "155") (name "unconnected-(U1B-P00.12-Pad108)") (class "Default")
      (node (ref "U1") (pin "108") (pinfunction "P00.12_108") (pintype "passive"))
    )
    (net (code "156") (name "unconnected-(U1B-P10.6{slash}#5-Pad90)") (class "Default")
      (node (ref "U1") (pin "90") (pinfunction "P10.6/#5_90") (pintype "passive"))
    )
    (net (code "157") (name "unconnected-(U1C-P10.5{slash}#4-Pad87)") (class "Default")
      (node (ref "U1") (pin "87") (pinfunction "P10.5/#4_87") (pintype "passive"))
    )
    (net (code "158") (name "unconnected-(U1C-P13.0-Pad74)") (class "Default")
      (node (ref "U1") (pin "74") (pinfunction "P13.0_74") (pintype "passive"))
    )
    (net (code "159") (name "unconnected-(U1C-P14.2{slash}#2-Pad71)") (class "Default")
      (node (ref "U1") (pin "71") (pinfunction "P14.2/#2_71") (pintype "passive"))
    )
    (net (code "160") (name "unconnected-(U1C-P14.3{slash}#3-Pad73)") (class "Default")
      (node (ref "U1") (pin "73") (pinfunction "P14.3/#3_73") (pintype "passive"))
    )
    (net (code "161") (name "unconnected-(U1C-P14.4{slash}#6-Pad70)") (class "Default")
      (node (ref "U1") (pin "70") (pinfunction "P14.4/#6_70") (pintype "passive"))
    )
    (net (code "162") (name "unconnected-(U1C-P14.5{slash}#1-Pad72)") (class "Default")
      (node (ref "U1") (pin "72") (pinfunction "P14.5/#1_72") (pintype "passive"))
    )
    (net (code "163") (name "unconnected-(U1C-P14.6{slash}#0-Pad75)") (class "Default")
      (node (ref "U1") (pin "75") (pinfunction "P14.6/#0_75") (pintype "passive"))
    )
    (net (code "164") (name "unconnected-(U1C-P15.0-Pad65)") (class "Default")
      (node (ref "U1") (pin "65") (pinfunction "P15.0_65") (pintype "passive"))
    )
    (net (code "165") (name "unconnected-(U1C-P15.3-Pad66)") (class "Default")
      (node (ref "U1") (pin "66") (pinfunction "P15.3_66") (pintype "passive"))
    )
    (net (code "166") (name "unconnected-(U1D-AN8-Pad8)") (class "Default")
      (node (ref "U1") (pin "8") (pinfunction "AN8_8") (pintype "passive"))
    )
    (net (code "167") (name "unconnected-(U1D-AN10-Pad3)") (class "Default")
      (node (ref "U1") (pin "3") (pinfunction "AN10_3") (pintype "passive"))
    )
    (net (code "168") (name "unconnected-(U1D-AN11-Pad4)") (class "Default")
      (node (ref "U1") (pin "4") (pinfunction "AN11_4") (pintype "passive"))
    )
    (net (code "169") (name "unconnected-(U1D-AN12-Pad1)") (class "Default")
      (node (ref "U1") (pin "1") (pinfunction "AN12_1") (pintype "passive"))
    )
    (net (code "170") (name "unconnected-(U1D-P33.4-Pad15)") (class "Default")
      (node (ref "U1") (pin "15") (pinfunction "P33.4_15") (pintype "passive"))
    )
    (net (code "171") (name "unconnected-(U1D-P33.5-Pad16)") (class "Default")
      (node (ref "U1") (pin "16") (pinfunction "P33.5_16") (pintype "passive"))
    )
    (net (code "172") (name "unconnected-(U1D-P33.8-Pad18)") (class "Default")
      (node (ref "U1") (pin "18") (pinfunction "P33.8_18") (pintype "passive"))
    )
    (net (code "173") (name "unconnected-(U1D-P33.10-Pad21)") (class "Default")
      (node (ref "U1") (pin "21") (pinfunction "P33.10_21") (pintype "passive"))
    )
    (net (code "174") (name "unconnected-(U1D-P33.13-Pad23)") (class "Default")
      (node (ref "U1") (pin "23") (pinfunction "P33.13_23") (pintype "passive"))
    )
    (net (code "175") (name "unconnected-(U1D-VREF+-Pad6)") (class "Default")
      (node (ref "U1") (pin "6") (pinfunction "VREF+_6") (pintype "passive"))
    )
    (net (code "176") (name "unconnected-(U1E-ESR0-Pad51)") (class "Default")
      (node (ref "U1") (pin "51") (pinfunction "ESR0_51") (pintype "passive"))
    )
    (net (code "177") (name "unconnected-(U1E-P15.4-Pad63)") (class "Default")
      (node (ref "U1") (pin "63") (pinfunction "P15.4_63") (pintype "passive"))
    )
    (net (code "178") (name "unconnected-(U1E-P20.6-Pad52)") (class "Default")
      (node (ref "U1") (pin "52") (pinfunction "P20.6_52") (pintype "passive"))
    )
    (net (code "179") (name "unconnected-(U1E-P20.9-Pad55)") (class "Default")
      (node (ref "U1") (pin "55") (pinfunction "P20.9_55") (pintype "passive"))
    )
    (net (code "180") (name "unconnected-(U1E-P22.0-Pad28)") (class "Default")
      (node (ref "U1") (pin "28") (pinfunction "P22.0_28") (pintype "passive"))
    )
    (net (code "181") (name "unconnected-(U1E-P22.1-Pad31)") (class "Default")
      (node (ref "U1") (pin "31") (pinfunction "P22.1_31") (pintype "passive"))
    )
    (net (code "182") (name "unconnected-(U1E-P22.2-Pad30)") (class "Default")
      (node (ref "U1") (pin "30") (pinfunction "P22.2_30") (pintype "passive"))
    )
    (net (code "183") (name "unconnected-(U1E-P32.0{slash}VG1N-Pad26)") (class "Default")
      (node (ref "U1") (pin "26") (pinfunction "P32.0/VG1N_26") (pintype "passive"))
    )
    (net (code "184") (name "unconnected-(U1E-P33.12-Pad27)") (class "Default")
      (node (ref "U1") (pin "27") (pinfunction "P33.12_27") (pintype "passive"))
    )
    (net (code "185") (name "unconnected-(U1E-VGATE1P-Pad25)") (class "Default")
      (node (ref "U1") (pin "25") (pinfunction "VGATE1P_25") (pintype "passive"))
    )
    (net (code "186") (name "unconnected-(U1F-ESR1-Pad50)") (class "Default")
      (node (ref "U1") (pin "50") (pinfunction "ESR1_50") (pintype "passive"))
    )
    (net (code "187") (name "unconnected-(U1F-P20.7-Pad53)") (class "Default")
      (node (ref "U1") (pin "53") (pinfunction "P20.7_53") (pintype "passive"))
    )
    (net (code "188") (name "unconnected-(U1F-P21.3-Pad38)") (class "Default")
      (node (ref "U1") (pin "38") (pinfunction "P21.3_38") (pintype "passive"))
    )
    (net (code "189") (name "unconnected-(U1F-P21.4-Pad41)") (class "Default")
      (node (ref "U1") (pin "41") (pinfunction "P21.4_41") (pintype "passive"))
    )
    (net (code "190") (name "unconnected-(U1F-P21.5-Pad44)") (class "Default")
      (node (ref "U1") (pin "44") (pinfunction "P21.5_44") (pintype "passive"))
    )
    (net (code "191") (name "unconnected-(U1F-P21.~{6}TDI-Pad47)") (class "Default")
      (node (ref "U1") (pin "47") (pinfunction "P21.~{6}TDI_47") (pintype "passive"))
    )
  )
)
